# Attenuverting_LinExp_VCA_Bottom.net
KiCad netlist of a schematic drawn in EAGLE
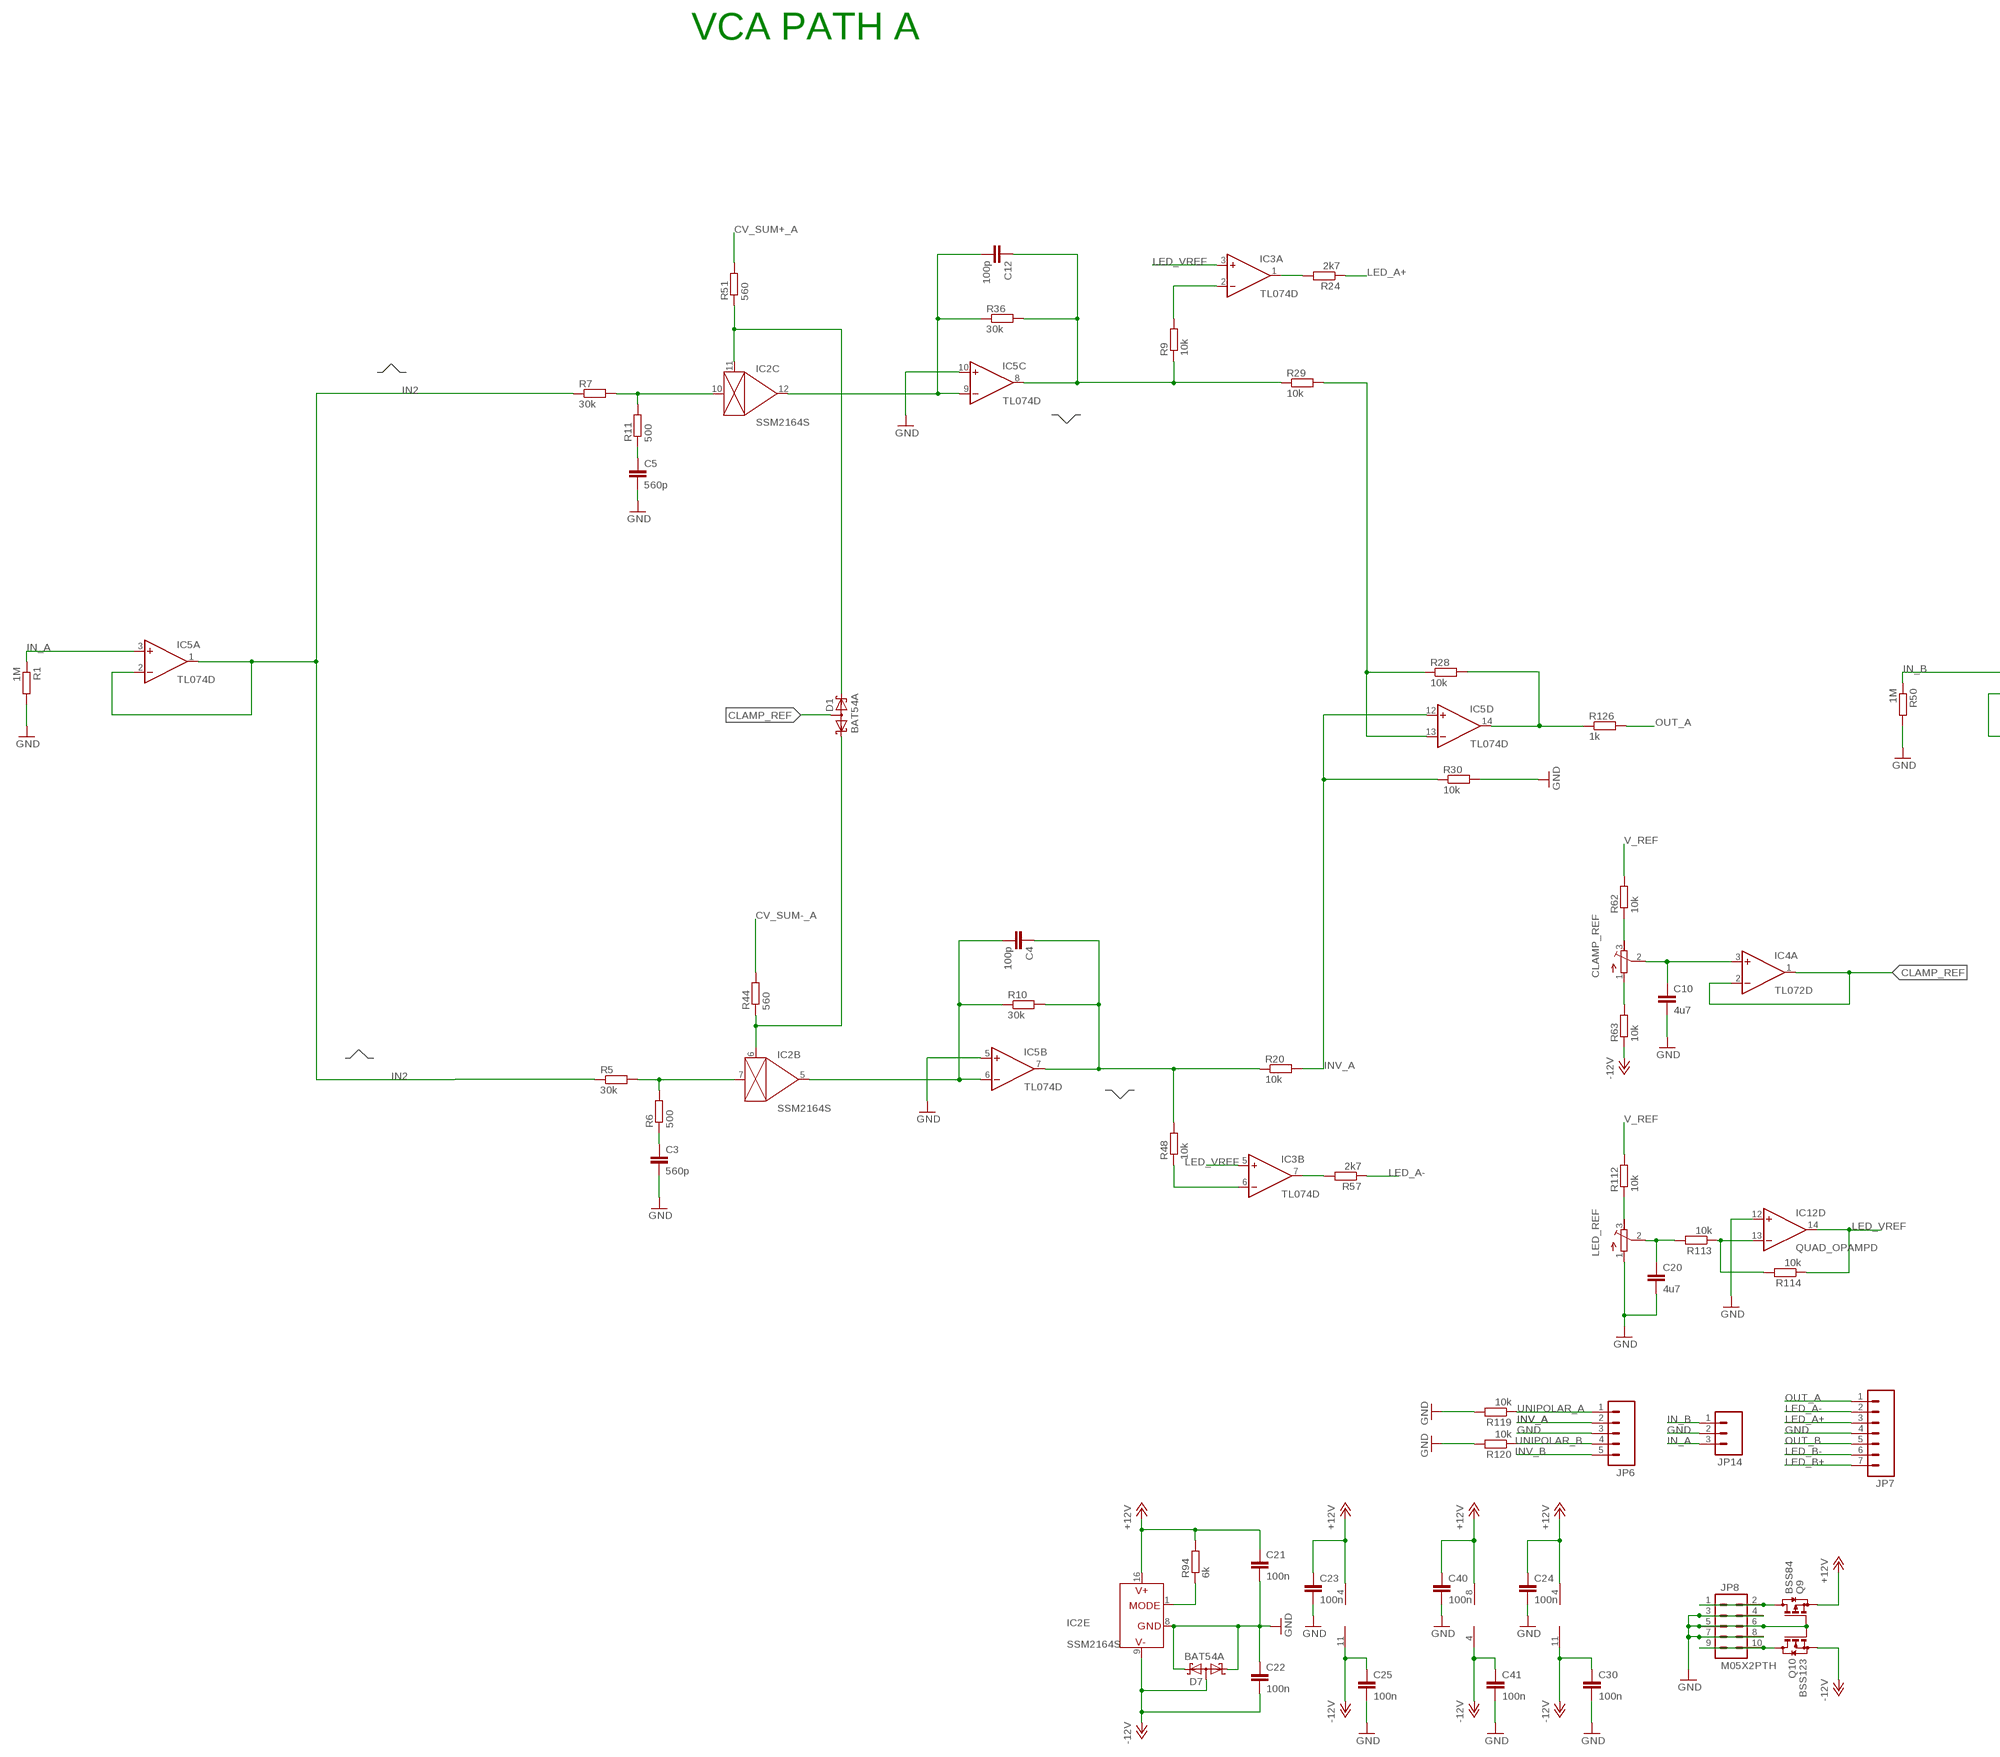
[diagram p0: schematic, sheet 1, part 1 of 2]
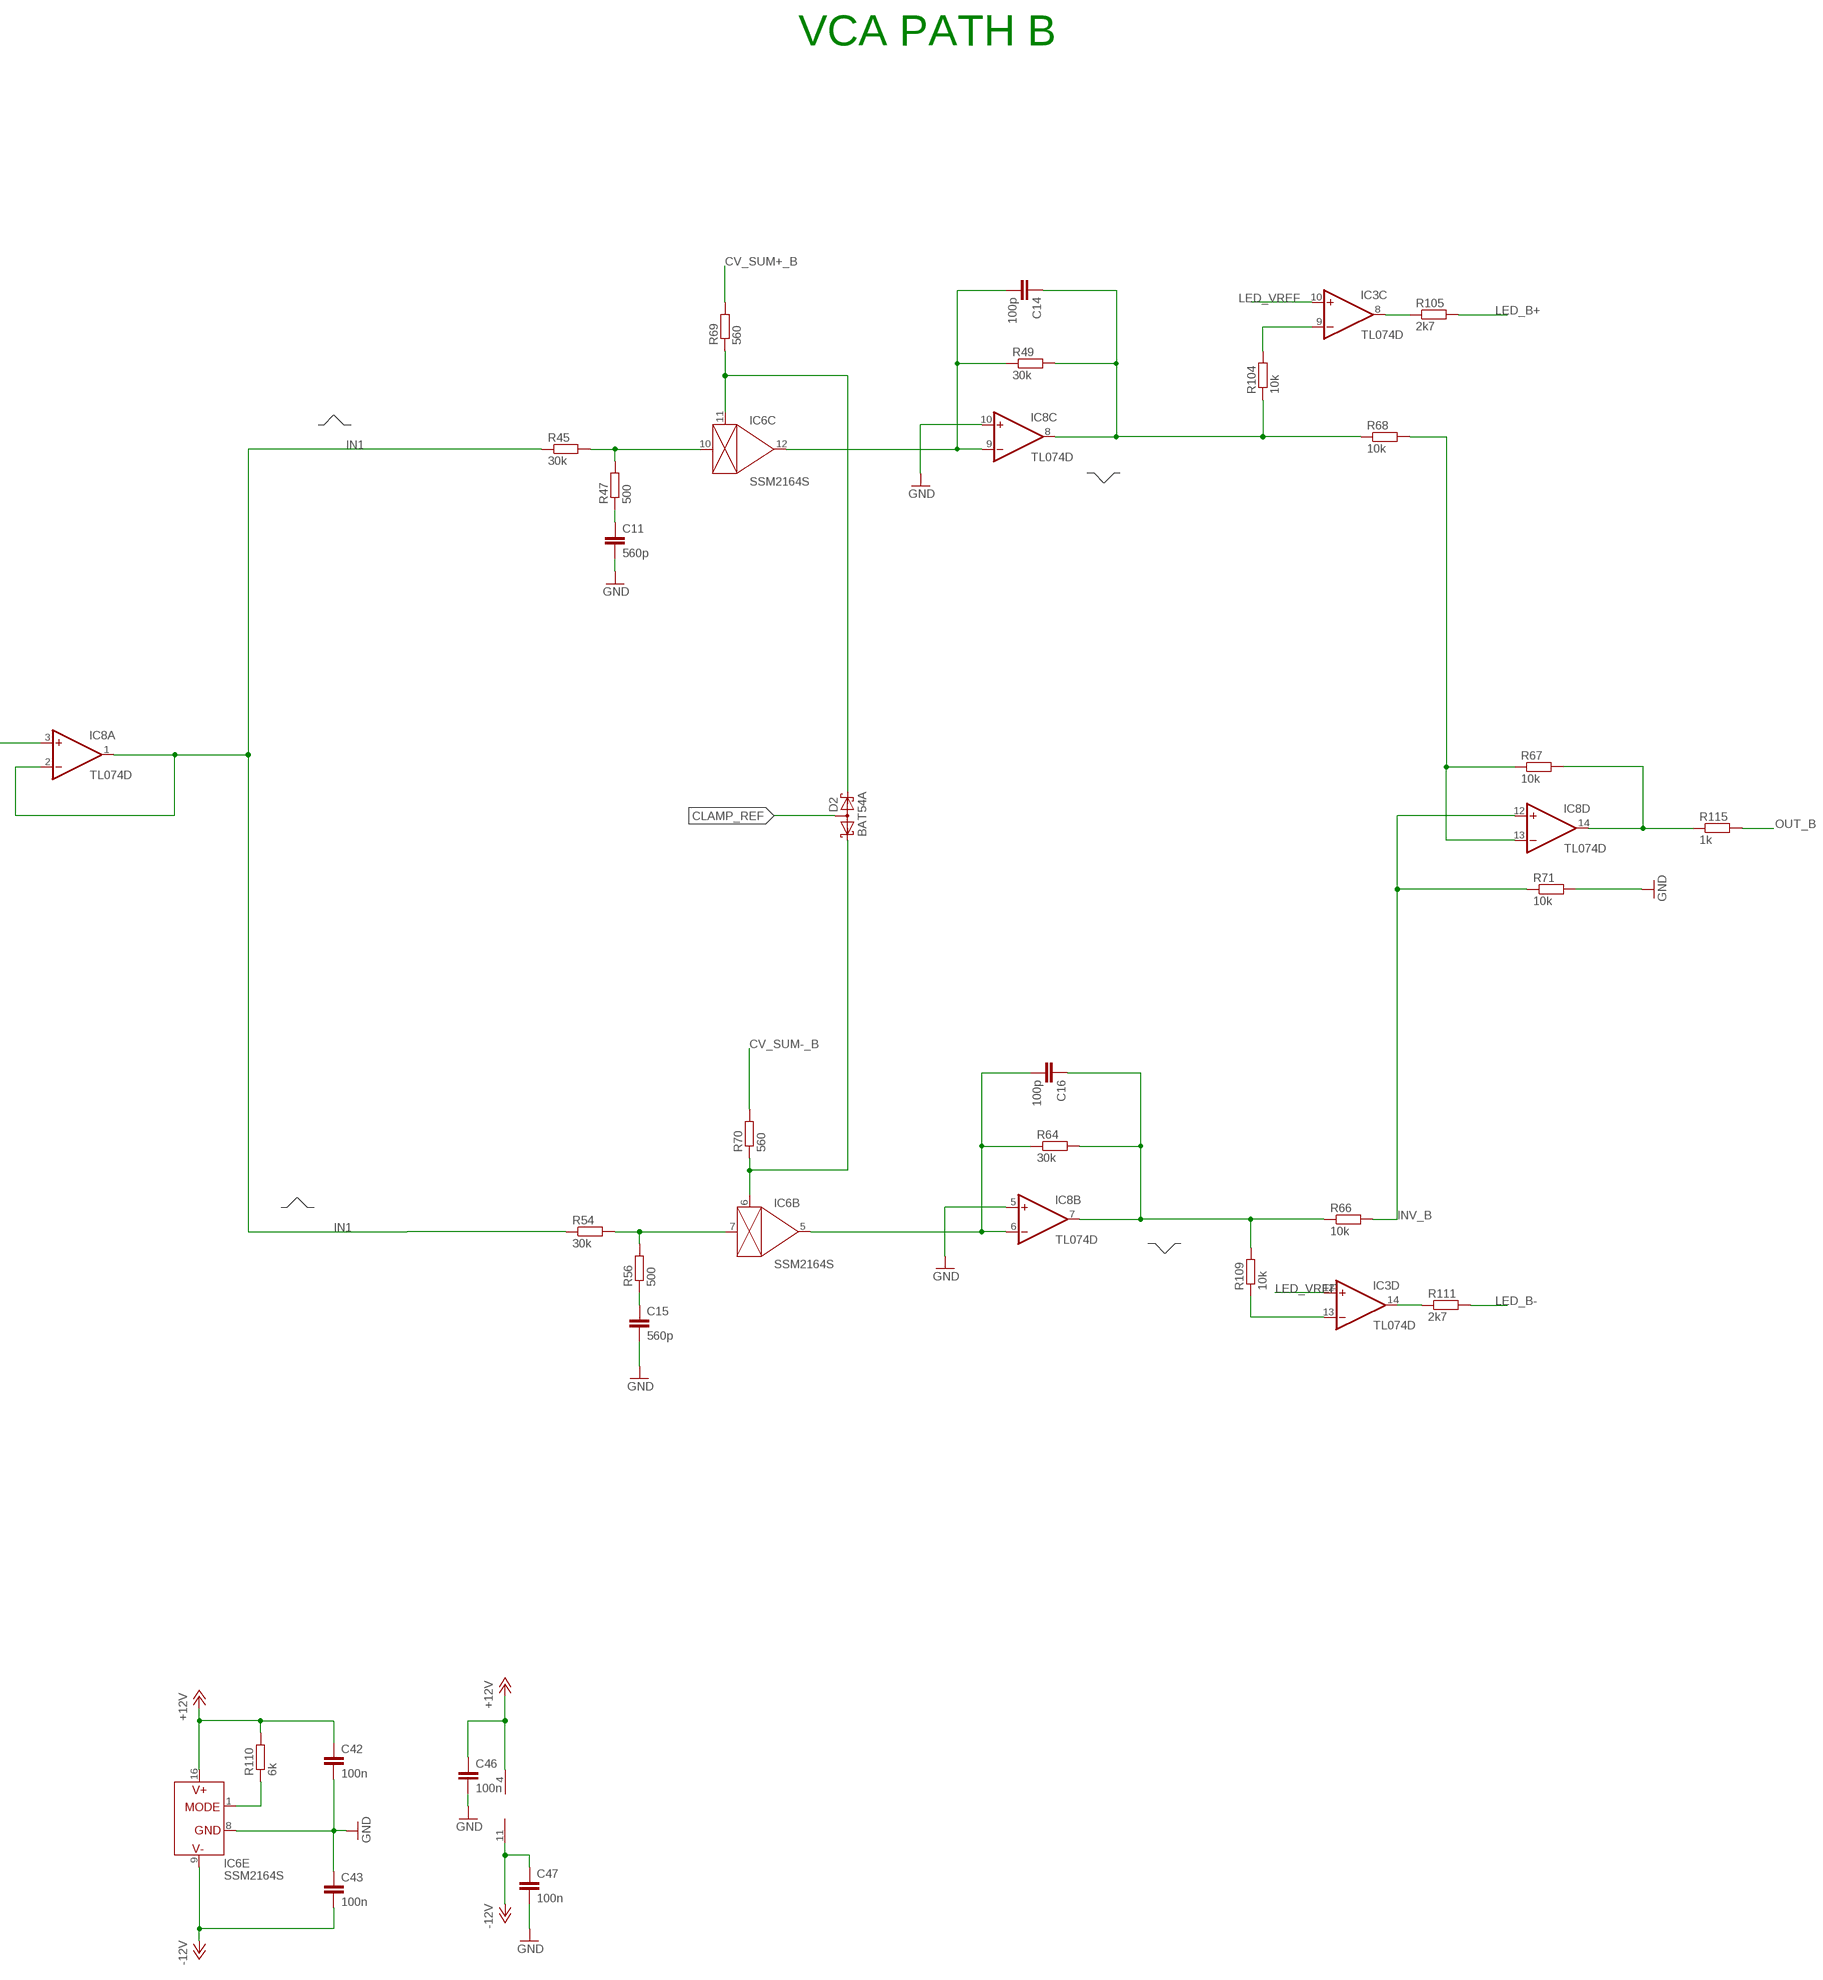
[diagram p1: schematic, sheet 1, part 2 of 2]
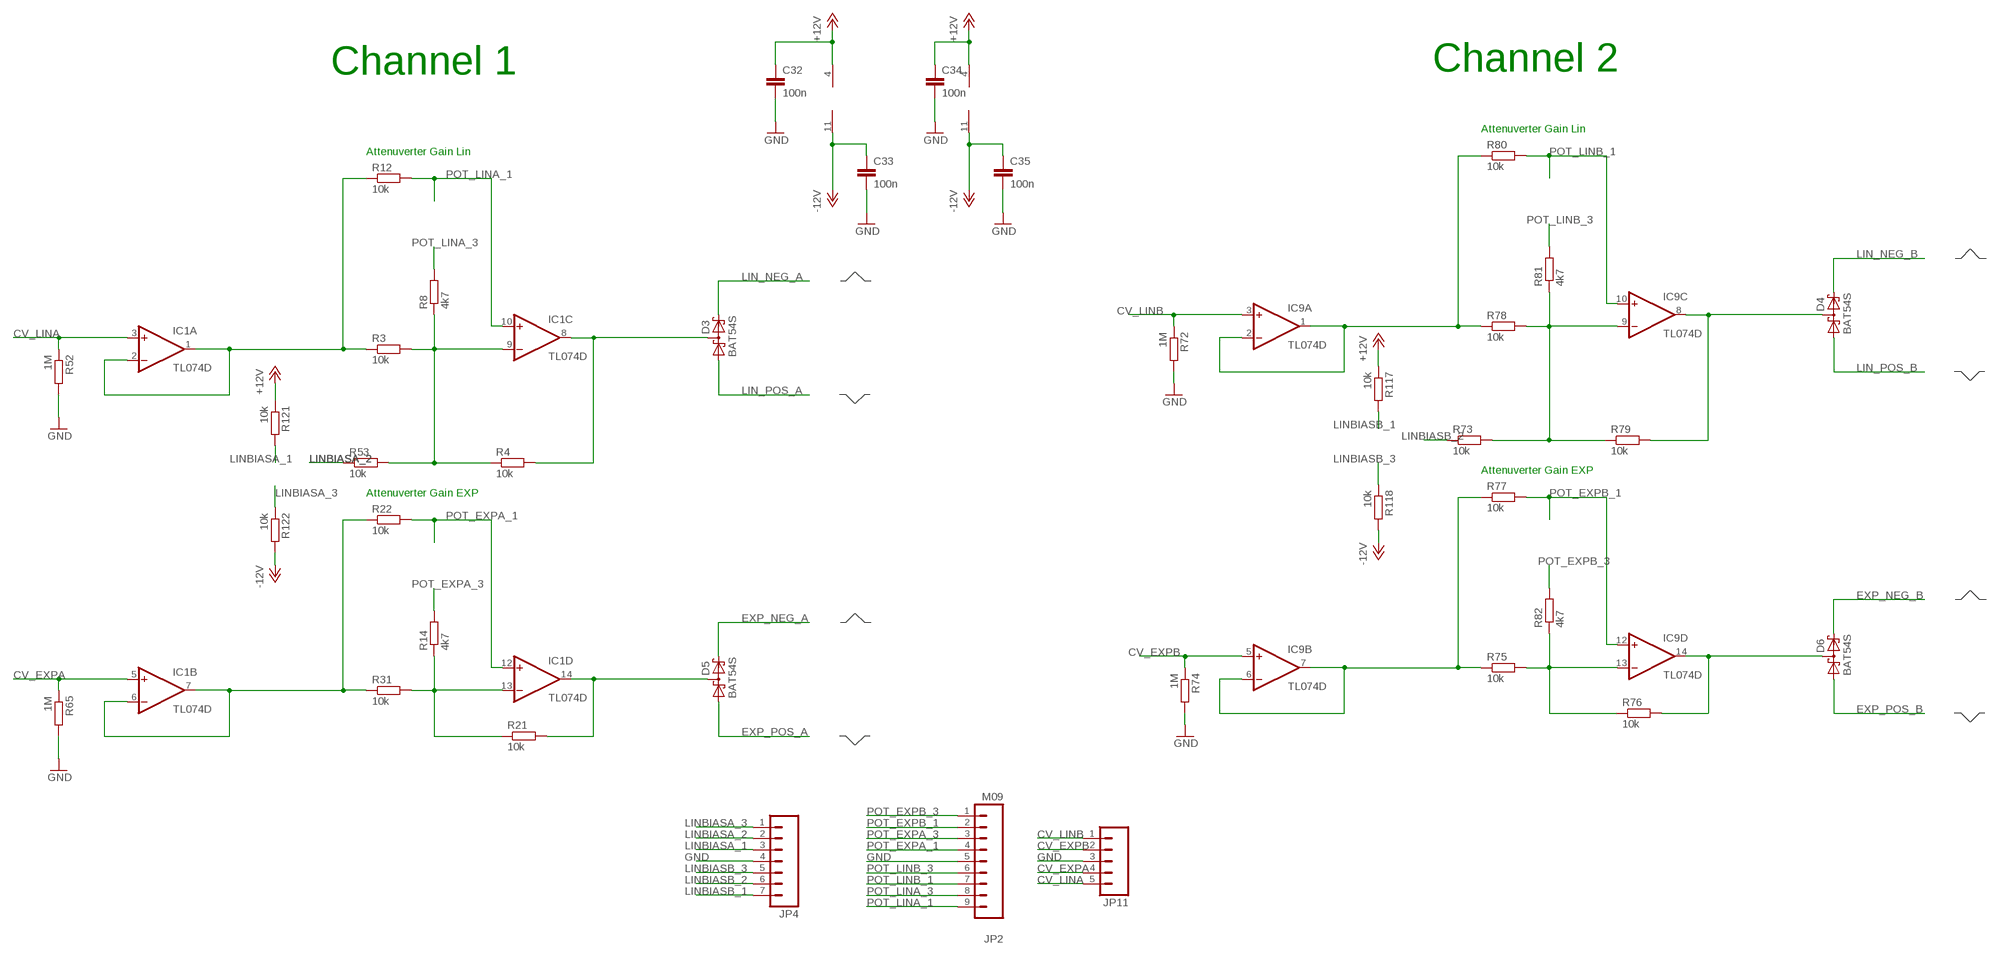
[diagram p2: schematic, sheet 2]
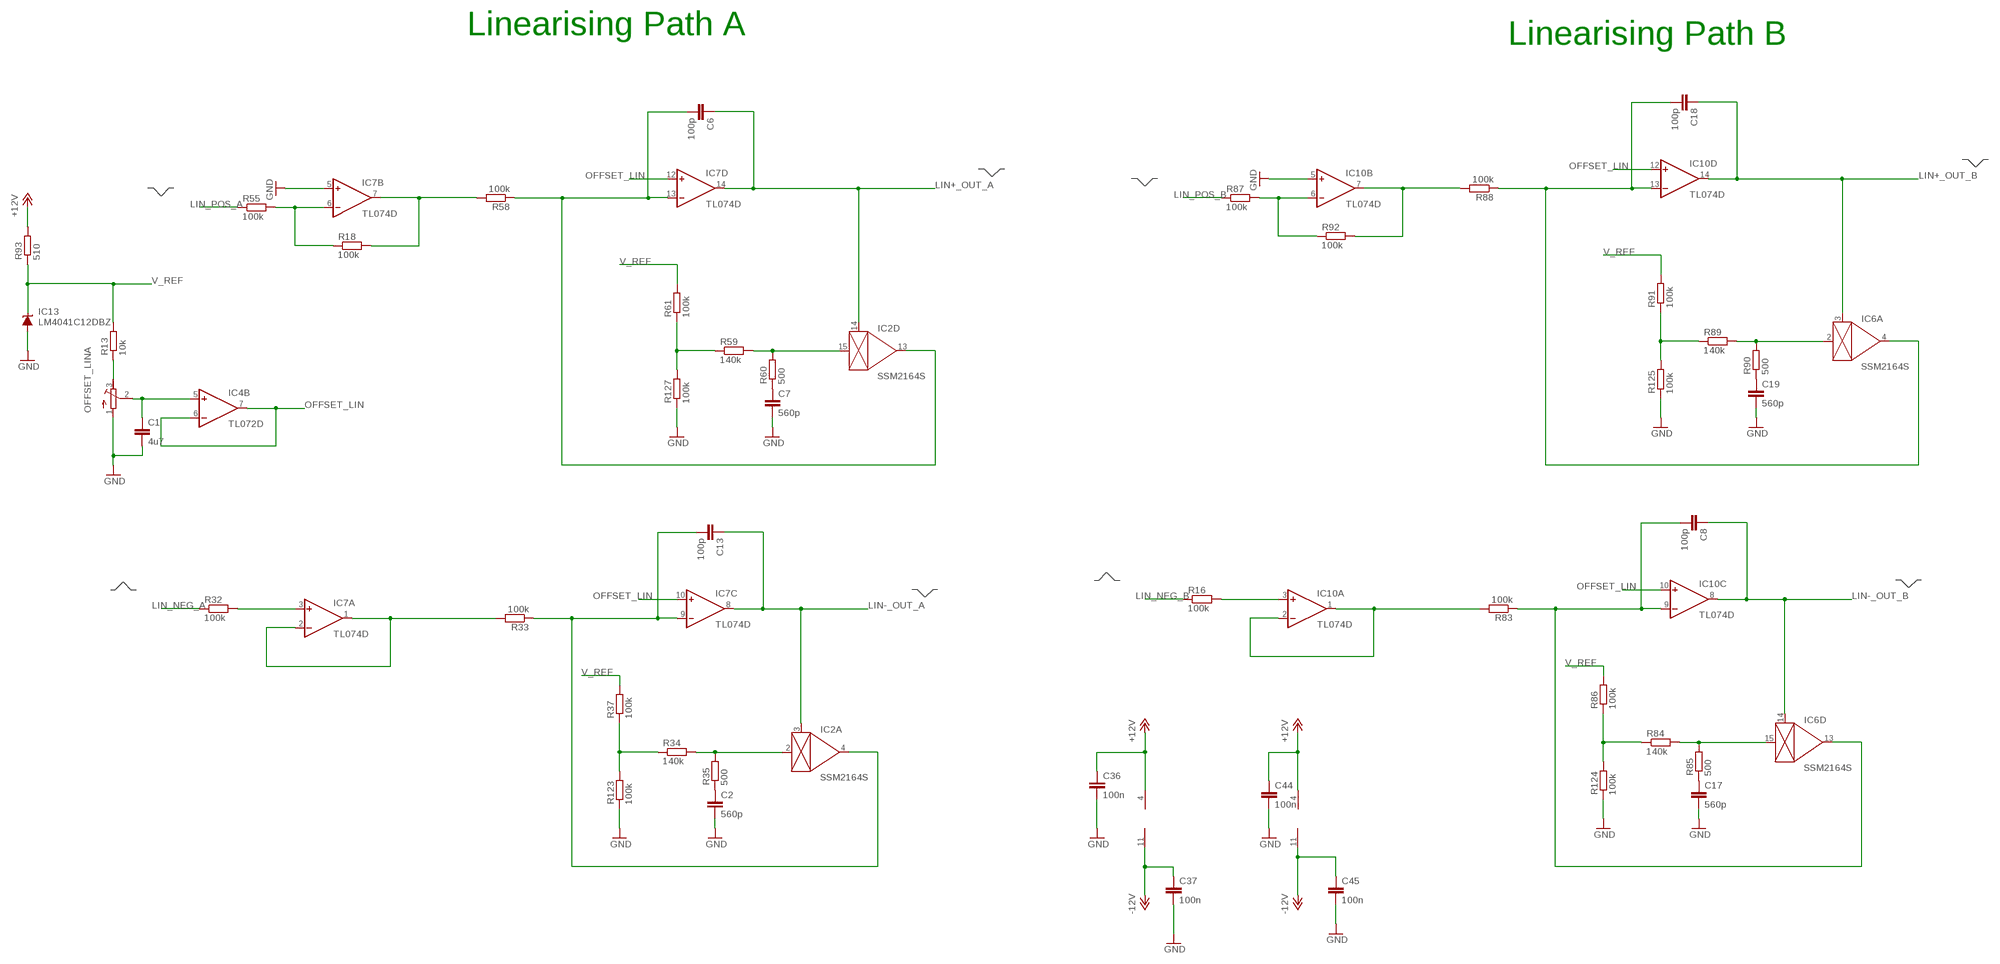
[diagram p3: schematic, sheet 3]
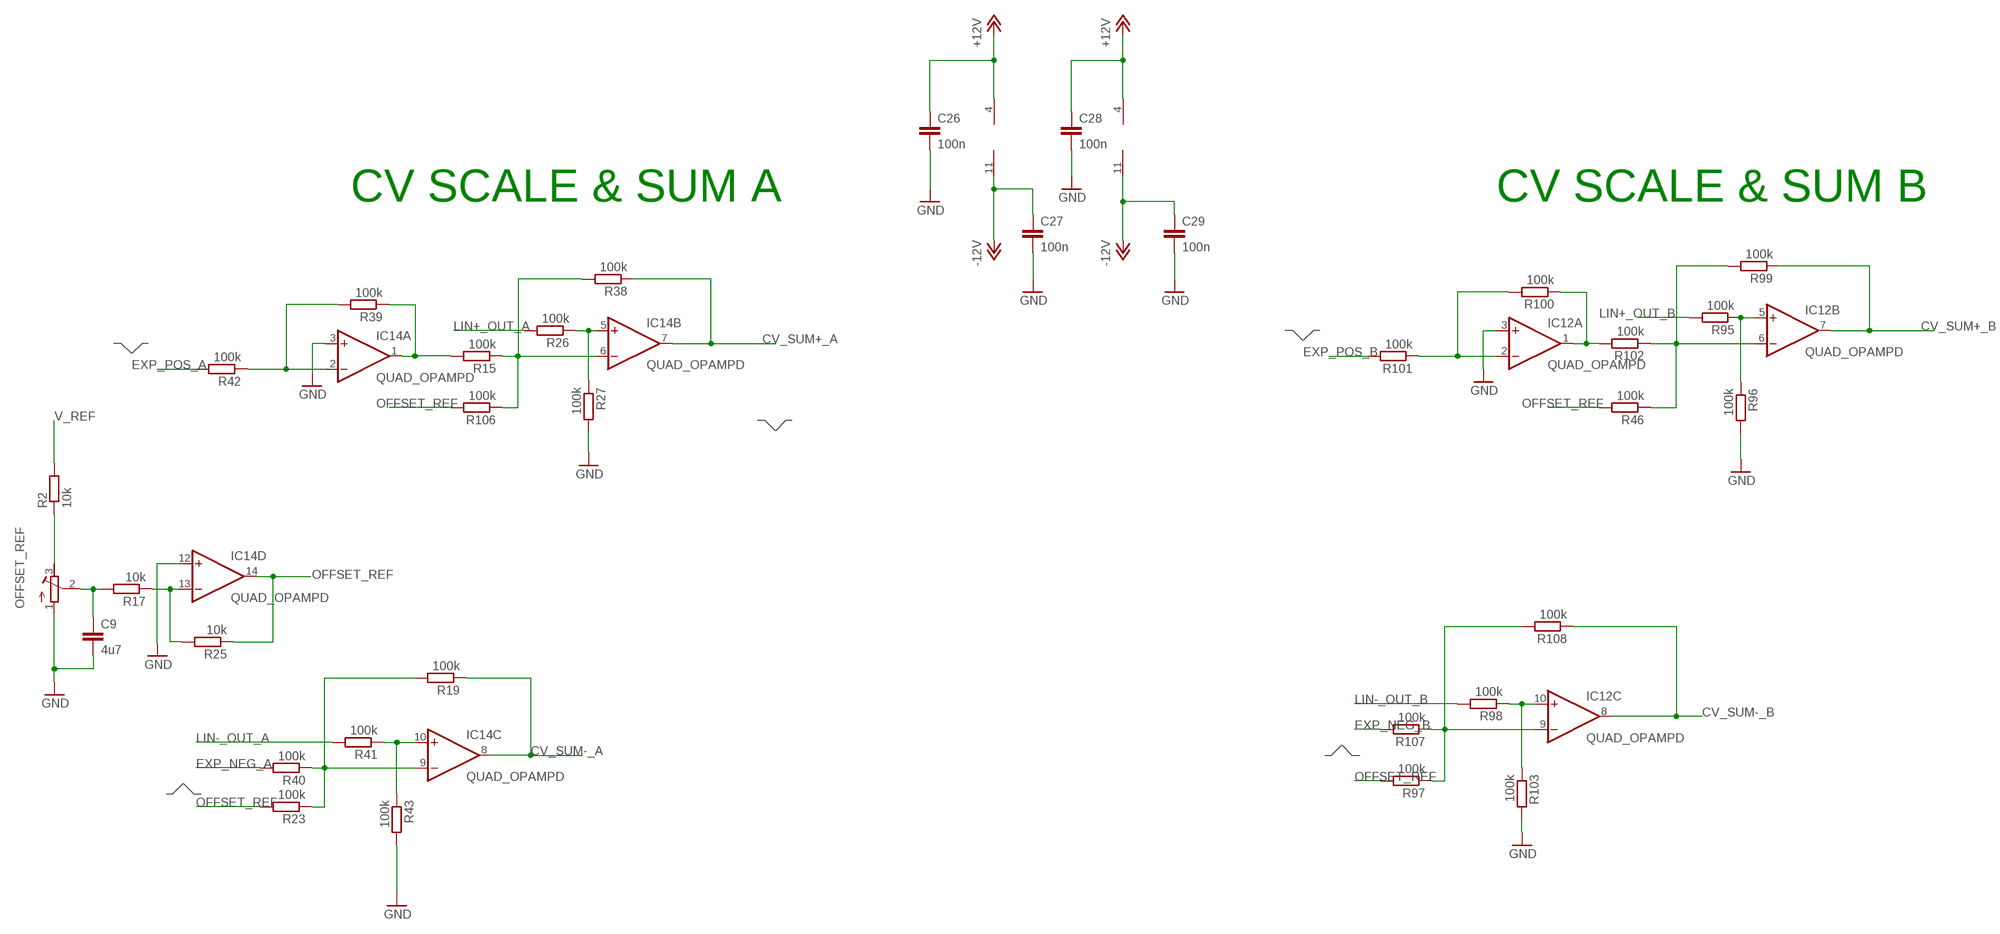
[diagram p4: schematic, sheet 4]

(export (version "E")
  (design (tool "Eeschema 10.0.6"))
  (components
    (comp (ref "C32")
      (value "100n")
      (footprint "eagle-import:C0603K")
      (libsource (lib "eagle-import") (part "C-EUC0603K"))
    )
    (comp (ref "C33")
      (value "100n")
      (footprint "eagle-import:C0603K")
      (libsource (lib "eagle-import") (part "C-EUC0603K"))
    )
    (comp (ref "C34")
      (value "100n")
      (footprint "eagle-import:C0603K")
      (libsource (lib "eagle-import") (part "C-EUC0603K"))
    )
    (comp (ref "C35")
      (value "100n")
      (footprint "eagle-import:C0603K")
      (libsource (lib "eagle-import") (part "C-EUC0603K"))
    )
    (comp (ref "D3")
      (value "BAT54S")
      (footprint "eagle-import:SOT23")
      (libsource (lib "eagle-import") (part "BAT54S"))
    )
    (comp (ref "D4")
      (value "BAT54S")
      (footprint "eagle-import:SOT23")
      (libsource (lib "eagle-import") (part "BAT54S"))
    )
    (comp (ref "D5")
      (value "BAT54S")
      (footprint "eagle-import:SOT23")
      (libsource (lib "eagle-import") (part "BAT54S"))
    )
    (comp (ref "D6")
      (value "BAT54S")
      (footprint "eagle-import:SOT23")
      (libsource (lib "eagle-import") (part "BAT54S"))
    )
    (comp (ref "IC1")
      (value "TL074D")
      (footprint "eagle-import:SO14")
      (fields (field (name "OC_FARNELL") "unknown"))
      (libsource (lib "eagle-import") (part "TL074D"))
    )
    (comp (ref "IC9")
      (value "TL074D")
      (footprint "eagle-import:SO14")
      (fields (field (name "OC_FARNELL") "unknown"))
      (libsource (lib "eagle-import") (part "TL074D"))
    )
    (comp (ref "JP2")
      (value "M09")
      (footprint "eagle-import:1X09")
      (libsource (lib "eagle-import") (part "M09"))
    )
    (comp (ref "JP4")
      (value "M07")
      (footprint "eagle-import:1X07")
      (libsource (lib "eagle-import") (part "M07"))
    )
    (comp (ref "JP11")
      (value "M05PTH")
      (footprint "eagle-import:1X05")
      (libsource (lib "eagle-import") (part "M05PTH"))
    )
    (comp (ref "R3")
      (value "10k")
      (footprint "eagle-import:0603")
      (libsource (lib "eagle-import") (part "R-EU_0603"))
    )
    (comp (ref "R4")
      (value "10k")
      (footprint "eagle-import:0603")
      (libsource (lib "eagle-import") (part "R-EU_0603"))
    )
    (comp (ref "R8")
      (value "4k7")
      (footprint "eagle-import:0603")
      (libsource (lib "eagle-import") (part "R-EU_0603"))
    )
    (comp (ref "R12")
      (value "10k")
      (footprint "eagle-import:0603")
      (libsource (lib "eagle-import") (part "R-EU_0603"))
    )
    (comp (ref "R14")
      (value "4k7")
      (footprint "eagle-import:0603")
      (libsource (lib "eagle-import") (part "R-EU_0603"))
    )
    (comp (ref "R21")
      (value "10k")
      (footprint "eagle-import:0603")
      (libsource (lib "eagle-import") (part "R-EU_0603"))
    )
    (comp (ref "R22")
      (value "10k")
      (footprint "eagle-import:0603")
      (libsource (lib "eagle-import") (part "R-EU_0603"))
    )
    (comp (ref "R31")
      (value "10k")
      (footprint "eagle-import:0603")
      (libsource (lib "eagle-import") (part "R-EU_0603"))
    )
    (comp (ref "R52")
      (value "1M")
      (footprint "eagle-import:0603")
      (libsource (lib "eagle-import") (part "R-EU_0603"))
    )
    (comp (ref "R53")
      (value "10k")
      (footprint "eagle-import:0603")
      (libsource (lib "eagle-import") (part "R-EU_0603"))
    )
    (comp (ref "R65")
      (value "1M")
      (footprint "eagle-import:0603")
      (libsource (lib "eagle-import") (part "R-EU_0603"))
    )
    (comp (ref "R72")
      (value "1M")
      (footprint "eagle-import:0603")
      (libsource (lib "eagle-import") (part "R-EU_0603"))
    )
    (comp (ref "R73")
      (value "10k")
      (footprint "eagle-import:0603")
      (libsource (lib "eagle-import") (part "R-EU_0603"))
    )
    (comp (ref "R74")
      (value "1M")
      (footprint "eagle-import:0603")
      (libsource (lib "eagle-import") (part "R-EU_0603"))
    )
    (comp (ref "R75")
      (value "10k")
      (footprint "eagle-import:0603")
      (libsource (lib "eagle-import") (part "R-EU_0603"))
    )
    (comp (ref "R76")
      (value "10k")
      (footprint "eagle-import:0603")
      (libsource (lib "eagle-import") (part "R-EU_0603"))
    )
    (comp (ref "R77")
      (value "10k")
      (footprint "eagle-import:0603")
      (libsource (lib "eagle-import") (part "R-EU_0603"))
    )
    (comp (ref "R78")
      (value "10k")
      (footprint "eagle-import:0603")
      (libsource (lib "eagle-import") (part "R-EU_0603"))
    )
    (comp (ref "R79")
      (value "10k")
      (footprint "eagle-import:0603")
      (libsource (lib "eagle-import") (part "R-EU_0603"))
    )
    (comp (ref "R80")
      (value "10k")
      (footprint "eagle-import:0603")
      (libsource (lib "eagle-import") (part "R-EU_0603"))
    )
    (comp (ref "R81")
      (value "4k7")
      (footprint "eagle-import:0603")
      (libsource (lib "eagle-import") (part "R-EU_0603"))
    )
    (comp (ref "R82")
      (value "4k7")
      (footprint "eagle-import:0603")
      (libsource (lib "eagle-import") (part "R-EU_0603"))
    )
    (comp (ref "R117")
      (value "10k")
      (footprint "eagle-import:0603")
      (libsource (lib "eagle-import") (part "R-EU_0603"))
    )
    (comp (ref "R118")
      (value "10k")
      (footprint "eagle-import:0603")
      (libsource (lib "eagle-import") (part "R-EU_0603"))
    )
    (comp (ref "R121")
      (value "10k")
      (footprint "eagle-import:0603")
      (libsource (lib "eagle-import") (part "R-EU_0603"))
    )
    (comp (ref "R122")
      (value "10k")
      (footprint "eagle-import:0603")
      (libsource (lib "eagle-import") (part "R-EU_0603"))
    )
    (comp (ref "C9")
      (value "4u7")
      (footprint "eagle-import:C0603K")
      (libsource (lib "eagle-import") (part "resistor_C-EUC0603K"))
    )
    (comp (ref "C26")
      (value "100n")
      (footprint "eagle-import:C0603K")
      (libsource (lib "eagle-import") (part "C-EUC0603K"))
    )
    (comp (ref "C27")
      (value "100n")
      (footprint "eagle-import:C0603K")
      (libsource (lib "eagle-import") (part "C-EUC0603K"))
    )
    (comp (ref "C28")
      (value "100n")
      (footprint "eagle-import:C0603K")
      (libsource (lib "eagle-import") (part "C-EUC0603K"))
    )
    (comp (ref "C29")
      (value "100n")
      (footprint "eagle-import:C0603K")
      (libsource (lib "eagle-import") (part "C-EUC0603K"))
    )
    (comp (ref "IC12")
      (value "QUAD_OPAMPD")
      (footprint "eagle-import:SO14")
      (libsource (lib "eagle-import") (part "QUAD_OPAMPD"))
    )
    (comp (ref "IC14")
      (value "QUAD_OPAMPD")
      (footprint "eagle-import:SO14")
      (libsource (lib "eagle-import") (part "QUAD_OPAMPD"))
    )
    (comp (ref "OFFSET_REF")
      (value "R-TRIMM64W")
      (footprint "eagle-import:RTRIM64W")
      (libsource (lib "eagle-import") (part "R-TRIMM64W"))
    )
    (comp (ref "R2")
      (value "10k")
      (footprint "eagle-import:0603")
      (libsource (lib "eagle-import") (part "R-EU_0603"))
    )
    (comp (ref "R15")
      (value "100k")
      (footprint "eagle-import:0603")
      (libsource (lib "eagle-import") (part "R-EU_0603"))
    )
    (comp (ref "R17")
      (value "10k")
      (footprint "eagle-import:0603")
      (libsource (lib "eagle-import") (part "R-EU_0603"))
    )
    (comp (ref "R19")
      (value "100k")
      (footprint "eagle-import:0603")
      (libsource (lib "eagle-import") (part "R-EU_0603"))
    )
    (comp (ref "R23")
      (value "100k")
      (footprint "eagle-import:0603")
      (libsource (lib "eagle-import") (part "R-EU_0603"))
    )
    (comp (ref "R25")
      (value "10k")
      (footprint "eagle-import:0603")
      (libsource (lib "eagle-import") (part "R-EU_0603"))
    )
    (comp (ref "R26")
      (value "100k")
      (footprint "eagle-import:0603")
      (libsource (lib "eagle-import") (part "R-EU_0603"))
    )
    (comp (ref "R27")
      (value "100k")
      (footprint "eagle-import:0603")
      (libsource (lib "eagle-import") (part "R-EU_0603"))
    )
    (comp (ref "R38")
      (value "100k")
      (footprint "eagle-import:0603")
      (libsource (lib "eagle-import") (part "R-EU_0603"))
    )
    (comp (ref "R39")
      (value "100k")
      (footprint "eagle-import:0603")
      (libsource (lib "eagle-import") (part "R-EU_0603"))
    )
    (comp (ref "R40")
      (value "100k")
      (footprint "eagle-import:0603")
      (libsource (lib "eagle-import") (part "R-EU_0603"))
    )
    (comp (ref "R41")
      (value "100k")
      (footprint "eagle-import:0603")
      (libsource (lib "eagle-import") (part "R-EU_0603"))
    )
    (comp (ref "R42")
      (value "100k")
      (footprint "eagle-import:0603")
      (libsource (lib "eagle-import") (part "R-EU_0603"))
    )
    (comp (ref "R43")
      (value "100k")
      (footprint "eagle-import:0603")
      (libsource (lib "eagle-import") (part "R-EU_0603"))
    )
    (comp (ref "R46")
      (value "100k")
      (footprint "eagle-import:0603")
      (libsource (lib "eagle-import") (part "R-EU_0603"))
    )
    (comp (ref "R95")
      (value "100k")
      (footprint "eagle-import:0603")
      (libsource (lib "eagle-import") (part "R-EU_0603"))
    )
    (comp (ref "R96")
      (value "100k")
      (footprint "eagle-import:0603")
      (libsource (lib "eagle-import") (part "R-EU_0603"))
    )
    (comp (ref "R97")
      (value "100k")
      (footprint "eagle-import:0603")
      (libsource (lib "eagle-import") (part "R-EU_0603"))
    )
    (comp (ref "R98")
      (value "100k")
      (footprint "eagle-import:0603")
      (libsource (lib "eagle-import") (part "R-EU_0603"))
    )
    (comp (ref "R99")
      (value "100k")
      (footprint "eagle-import:0603")
      (libsource (lib "eagle-import") (part "R-EU_0603"))
    )
    (comp (ref "R100")
      (value "100k")
      (footprint "eagle-import:0603")
      (libsource (lib "eagle-import") (part "R-EU_0603"))
    )
    (comp (ref "R101")
      (value "100k")
      (footprint "eagle-import:0603")
      (libsource (lib "eagle-import") (part "R-EU_0603"))
    )
    (comp (ref "R102")
      (value "100k")
      (footprint "eagle-import:0603")
      (libsource (lib "eagle-import") (part "R-EU_0603"))
    )
    (comp (ref "R103")
      (value "100k")
      (footprint "eagle-import:0603")
      (libsource (lib "eagle-import") (part "R-EU_0603"))
    )
    (comp (ref "R106")
      (value "100k")
      (footprint "eagle-import:0603")
      (libsource (lib "eagle-import") (part "R-EU_0603"))
    )
    (comp (ref "R107")
      (value "100k")
      (footprint "eagle-import:0603")
      (libsource (lib "eagle-import") (part "R-EU_0603"))
    )
    (comp (ref "R108")
      (value "100k")
      (footprint "eagle-import:0603")
      (libsource (lib "eagle-import") (part "R-EU_0603"))
    )
    (comp (ref "C1")
      (value "4u7")
      (footprint "eagle-import:C0603K")
      (libsource (lib "eagle-import") (part "resistor_C-EUC0603K"))
    )
    (comp (ref "C2")
      (value "560p")
      (footprint "eagle-import:C0603K")
      (libsource (lib "eagle-import") (part "resistor_C-EUC0603K"))
    )
    (comp (ref "C6")
      (value "100p")
      (footprint "eagle-import:C0603K")
      (libsource (lib "eagle-import") (part "resistor_C-EUC0603K"))
    )
    (comp (ref "C7")
      (value "560p")
      (footprint "eagle-import:C0603K")
      (libsource (lib "eagle-import") (part "resistor_C-EUC0603K"))
    )
    (comp (ref "C8")
      (value "100p")
      (footprint "eagle-import:C0603K")
      (libsource (lib "eagle-import") (part "resistor_C-EUC0603K"))
    )
    (comp (ref "C13")
      (value "100p")
      (footprint "eagle-import:C0603K")
      (libsource (lib "eagle-import") (part "resistor_C-EUC0603K"))
    )
    (comp (ref "C17")
      (value "560p")
      (footprint "eagle-import:C0603K")
      (libsource (lib "eagle-import") (part "resistor_C-EUC0603K"))
    )
    (comp (ref "C18")
      (value "100p")
      (footprint "eagle-import:C0603K")
      (libsource (lib "eagle-import") (part "resistor_C-EUC0603K"))
    )
    (comp (ref "C19")
      (value "560p")
      (footprint "eagle-import:C0603K")
      (libsource (lib "eagle-import") (part "resistor_C-EUC0603K"))
    )
    (comp (ref "C36")
      (value "100n")
      (footprint "eagle-import:C0603K")
      (libsource (lib "eagle-import") (part "rcl@1_C-EUC0603K"))
    )
    (comp (ref "C37")
      (value "100n")
      (footprint "eagle-import:C0603K")
      (libsource (lib "eagle-import") (part "rcl@1_C-EUC0603K"))
    )
    (comp (ref "C44")
      (value "100n")
      (footprint "eagle-import:C0603K")
      (libsource (lib "eagle-import") (part "rcl@1_C-EUC0603K"))
    )
    (comp (ref "C45")
      (value "100n")
      (footprint "eagle-import:C0603K")
      (libsource (lib "eagle-import") (part "rcl@1_C-EUC0603K"))
    )
    (comp (ref "IC2")
      (value "SSM2164S")
      (footprint "eagle-import:SOIC16N")
      (fields (field (name "OC_FARNELL") "unknown"))
      (libsource (lib "eagle-import") (part "SSM2164S"))
    )
    (comp (ref "IC4")
      (value "TL072D")
      (footprint "eagle-import:SO08")
      (libsource (lib "eagle-import") (part "TL072D"))
    )
    (comp (ref "IC6")
      (value "SSM2164S")
      (footprint "eagle-import:SOIC16N")
      (fields (field (name "OC_FARNELL") "unknown"))
      (libsource (lib "eagle-import") (part "SSM2164S"))
    )
    (comp (ref "IC7")
      (value "TL074D")
      (footprint "eagle-import:SO14")
      (fields (field (name "OC_FARNELL") "unknown"))
      (libsource (lib "eagle-import") (part "TL074D"))
    )
    (comp (ref "IC10")
      (value "TL074D")
      (footprint "eagle-import:SO14")
      (fields (field (name "OC_FARNELL") "unknown"))
      (libsource (lib "eagle-import") (part "TL074D"))
    )
    (comp (ref "IC13")
      (value "LM4041C12DBZ")
      (footprint "eagle-import:DBZ_R-PDSO-G3")
      (fields (field (name "MF") "TEXAS INSTRUMENT CONNECTORS") (field (name "MPN") "LM4041C12QDBZT"))
      (libsource (lib "eagle-import") (part "LM4041DBZC12"))
    )
    (comp (ref "OFFSET_LINA")
      (value "R-TRIMM64W")
      (footprint "eagle-import:RTRIM64W")
      (libsource (lib "eagle-import") (part "R-TRIMM64W"))
    )
    (comp (ref "R13")
      (value "10k")
      (footprint "eagle-import:0603")
      (libsource (lib "eagle-import") (part "R-EU_0603"))
    )
    (comp (ref "R16")
      (value "100k")
      (footprint "eagle-import:0603")
      (libsource (lib "eagle-import") (part "R-EU_0603"))
    )
    (comp (ref "R18")
      (value "100k")
      (footprint "eagle-import:0603")
      (libsource (lib "eagle-import") (part "R-EU_0603"))
    )
    (comp (ref "R32")
      (value "100k")
      (footprint "eagle-import:0603")
      (libsource (lib "eagle-import") (part "R-EU_0603"))
    )
    (comp (ref "R33")
      (value "100k")
      (footprint "eagle-import:0603")
      (libsource (lib "eagle-import") (part "R-EU_0603"))
    )
    (comp (ref "R34")
      (value "140k")
      (footprint "eagle-import:0603")
      (libsource (lib "eagle-import") (part "R-EU_0603"))
    )
    (comp (ref "R35")
      (value "500")
      (footprint "eagle-import:0603")
      (libsource (lib "eagle-import") (part "R-EU_0603"))
    )
    (comp (ref "R37")
      (value "100k")
      (footprint "eagle-import:0603")
      (libsource (lib "eagle-import") (part "R-EU_0603"))
    )
    (comp (ref "R55")
      (value "100k")
      (footprint "eagle-import:0603")
      (libsource (lib "eagle-import") (part "R-EU_0603"))
    )
    (comp (ref "R58")
      (value "100k")
      (footprint "eagle-import:0603")
      (libsource (lib "eagle-import") (part "R-EU_0603"))
    )
    (comp (ref "R59")
      (value "140k")
      (footprint "eagle-import:0603")
      (libsource (lib "eagle-import") (part "R-EU_0603"))
    )
    (comp (ref "R60")
      (value "500")
      (footprint "eagle-import:0603")
      (libsource (lib "eagle-import") (part "R-EU_0603"))
    )
    (comp (ref "R61")
      (value "100k")
      (footprint "eagle-import:0603")
      (libsource (lib "eagle-import") (part "R-EU_0603"))
    )
    (comp (ref "R83")
      (value "100k")
      (footprint "eagle-import:0603")
      (libsource (lib "eagle-import") (part "R-EU_0603"))
    )
    (comp (ref "R84")
      (value "140k")
      (footprint "eagle-import:0603")
      (libsource (lib "eagle-import") (part "R-EU_0603"))
    )
    (comp (ref "R85")
      (value "500")
      (footprint "eagle-import:0603")
      (libsource (lib "eagle-import") (part "R-EU_0603"))
    )
    (comp (ref "R86")
      (value "100k")
      (footprint "eagle-import:0603")
      (libsource (lib "eagle-import") (part "R-EU_0603"))
    )
    (comp (ref "R87")
      (value "100k")
      (footprint "eagle-import:0603")
      (libsource (lib "eagle-import") (part "R-EU_0603"))
    )
    (comp (ref "R88")
      (value "100k")
      (footprint "eagle-import:0603")
      (libsource (lib "eagle-import") (part "R-EU_0603"))
    )
    (comp (ref "R89")
      (value "140k")
      (footprint "eagle-import:0603")
      (libsource (lib "eagle-import") (part "R-EU_0603"))
    )
    (comp (ref "R90")
      (value "500")
      (footprint "eagle-import:0603")
      (libsource (lib "eagle-import") (part "R-EU_0603"))
    )
    (comp (ref "R91")
      (value "100k")
      (footprint "eagle-import:0603")
      (libsource (lib "eagle-import") (part "R-EU_0603"))
    )
    (comp (ref "R92")
      (value "100k")
      (footprint "eagle-import:0603")
      (libsource (lib "eagle-import") (part "R-EU_0603"))
    )
    (comp (ref "R93")
      (value "510")
      (footprint "eagle-import:0603")
      (libsource (lib "eagle-import") (part "R-EU_0603"))
    )
    (comp (ref "R123")
      (value "100k")
      (footprint "eagle-import:0603")
      (libsource (lib "eagle-import") (part "R-EU_0603"))
    )
    (comp (ref "R124")
      (value "100k")
      (footprint "eagle-import:0603")
      (libsource (lib "eagle-import") (part "R-EU_0603"))
    )
    (comp (ref "R125")
      (value "100k")
      (footprint "eagle-import:0603")
      (libsource (lib "eagle-import") (part "R-EU_0603"))
    )
    (comp (ref "R127")
      (value "100k")
      (footprint "eagle-import:0603")
      (libsource (lib "eagle-import") (part "R-EU_0603"))
    )
    (comp (ref "C3")
      (value "560p")
      (footprint "eagle-import:C0603K")
      (libsource (lib "eagle-import") (part "resistor_C-EUC0603K"))
    )
    (comp (ref "C4")
      (value "100p")
      (footprint "eagle-import:C0603K")
      (libsource (lib "eagle-import") (part "resistor_C-EUC0603K"))
    )
    (comp (ref "C5")
      (value "560p")
      (footprint "eagle-import:C0603K")
      (libsource (lib "eagle-import") (part "resistor_C-EUC0603K"))
    )
    (comp (ref "C10")
      (value "4u7")
      (footprint "eagle-import:C0603K")
      (libsource (lib "eagle-import") (part "resistor_C-EUC0603K"))
    )
    (comp (ref "C11")
      (value "560p")
      (footprint "eagle-import:C0603K")
      (libsource (lib "eagle-import") (part "resistor_C-EUC0603K"))
    )
    (comp (ref "C12")
      (value "100p")
      (footprint "eagle-import:C0603K")
      (libsource (lib "eagle-import") (part "resistor_C-EUC0603K"))
    )
    (comp (ref "C14")
      (value "100p")
      (footprint "eagle-import:C0603K")
      (libsource (lib "eagle-import") (part "resistor_C-EUC0603K"))
    )
    (comp (ref "C15")
      (value "560p")
      (footprint "eagle-import:C0603K")
      (libsource (lib "eagle-import") (part "resistor_C-EUC0603K"))
    )
    (comp (ref "C16")
      (value "100p")
      (footprint "eagle-import:C0603K")
      (libsource (lib "eagle-import") (part "resistor_C-EUC0603K"))
    )
    (comp (ref "C20")
      (value "4u7")
      (footprint "eagle-import:C0603K")
      (libsource (lib "eagle-import") (part "resistor_C-EUC0603K"))
    )
    (comp (ref "C21")
      (value "100n")
      (footprint "eagle-import:C0603K")
      (libsource (lib "eagle-import") (part "C-EUC0603K"))
    )
    (comp (ref "C22")
      (value "100n")
      (footprint "eagle-import:C0603K")
      (libsource (lib "eagle-import") (part "C-EUC0603K"))
    )
    (comp (ref "C23")
      (value "100n")
      (footprint "eagle-import:C0603K")
      (libsource (lib "eagle-import") (part "C-EUC0603K"))
    )
    (comp (ref "C24")
      (value "100n")
      (footprint "eagle-import:C0603K")
      (libsource (lib "eagle-import") (part "C-EUC0603K"))
    )
    (comp (ref "C25")
      (value "100n")
      (footprint "eagle-import:C0603K")
      (libsource (lib "eagle-import") (part "C-EUC0603K"))
    )
    (comp (ref "C30")
      (value "100n")
      (footprint "eagle-import:C0603K")
      (libsource (lib "eagle-import") (part "C-EUC0603K"))
    )
    (comp (ref "C40")
      (value "100n")
      (footprint "eagle-import:C0603K")
      (libsource (lib "eagle-import") (part "C-EUC0603K"))
    )
    (comp (ref "C41")
      (value "100n")
      (footprint "eagle-import:C0603K")
      (libsource (lib "eagle-import") (part "C-EUC0603K"))
    )
    (comp (ref "C42")
      (value "100n")
      (footprint "eagle-import:C0603K")
      (libsource (lib "eagle-import") (part "C-EUC0603K"))
    )
    (comp (ref "C43")
      (value "100n")
      (footprint "eagle-import:C0603K")
      (libsource (lib "eagle-import") (part "C-EUC0603K"))
    )
    (comp (ref "C46")
      (value "100n")
      (footprint "eagle-import:C0603K")
      (libsource (lib "eagle-import") (part "C-EUC0603K"))
    )
    (comp (ref "C47")
      (value "100n")
      (footprint "eagle-import:C0603K")
      (libsource (lib "eagle-import") (part "C-EUC0603K"))
    )
    (comp (ref "CLAMP_REF")
      (value "R-TRIMM64W")
      (footprint "eagle-import:RTRIM64W")
      (libsource (lib "eagle-import") (part "R-TRIMM64W"))
    )
    (comp (ref "D1")
      (value "BAT54A")
      (footprint "eagle-import:SOT23")
      (libsource (lib "eagle-import") (part "BAT54A"))
    )
    (comp (ref "D2")
      (value "BAT54A")
      (footprint "eagle-import:SOT23")
      (libsource (lib "eagle-import") (part "BAT54A"))
    )
    (comp (ref "D7")
      (value "BAT54A")
      (footprint "eagle-import:SOT23")
      (libsource (lib "eagle-import") (part "BAT54A"))
    )
    (comp (ref "IC3")
      (value "TL074D")
      (footprint "eagle-import:SO14")
      (libsource (lib "eagle-import") (part "linear@1_TL074D"))
    )
    (comp (ref "IC5")
      (value "TL074D")
      (footprint "eagle-import:SO14")
      (fields (field (name "OC_FARNELL") "unknown"))
      (libsource (lib "eagle-import") (part "TL074D"))
    )
    (comp (ref "IC8")
      (value "TL074D")
      (footprint "eagle-import:SO14")
      (fields (field (name "OC_FARNELL") "unknown"))
      (libsource (lib "eagle-import") (part "TL074D"))
    )
    (comp (ref "JP6")
      (value "M05PTH")
      (footprint "eagle-import:1X05")
      (libsource (lib "eagle-import") (part "M05PTH"))
    )
    (comp (ref "JP7")
      (value "M07")
      (footprint "eagle-import:1X07")
      (libsource (lib "eagle-import") (part "M07"))
    )
    (comp (ref "JP8")
      (value "M05X2PTH")
      (footprint "eagle-import:AVR_ICSP")
      (libsource (lib "eagle-import") (part "M05X2PTH"))
    )
    (comp (ref "JP14")
      (value "M03PTH")
      (footprint "eagle-import:1X03")
      (libsource (lib "eagle-import") (part "M03PTH"))
    )
    (comp (ref "LED_REF")
      (value "R-TRIMM64W")
      (footprint "eagle-import:RTRIM64W")
      (libsource (lib "eagle-import") (part "R-TRIMM64W"))
    )
    (comp (ref "Q9")
      (value "BSS84")
      (footprint "eagle-import:SOT23")
      (libsource (lib "eagle-import") (part "BSS84"))
    )
    (comp (ref "Q10")
      (value "BSS123")
      (footprint "eagle-import:SOT23")
      (libsource (lib "eagle-import") (part "BSS123"))
    )
    (comp (ref "R1")
      (value "1M")
      (footprint "eagle-import:0603")
      (libsource (lib "eagle-import") (part "R-EU_0603"))
    )
    (comp (ref "R5")
      (value "30k")
      (footprint "eagle-import:0603")
      (libsource (lib "eagle-import") (part "R-EU_0603"))
    )
    (comp (ref "R6")
      (value "500")
      (footprint "eagle-import:0603")
      (libsource (lib "eagle-import") (part "R-EU_0603"))
    )
    (comp (ref "R7")
      (value "30k")
      (footprint "eagle-import:0603")
      (libsource (lib "eagle-import") (part "R-EU_0603"))
    )
    (comp (ref "R9")
      (value "10k")
      (footprint "eagle-import:0603")
      (libsource (lib "eagle-import") (part "R-EU_0603"))
    )
    (comp (ref "R10")
      (value "30k")
      (footprint "eagle-import:0603")
      (libsource (lib "eagle-import") (part "R-EU_0603"))
    )
    (comp (ref "R11")
      (value "500")
      (footprint "eagle-import:0603")
      (libsource (lib "eagle-import") (part "R-EU_0603"))
    )
    (comp (ref "R20")
      (value "10k")
      (footprint "eagle-import:0603")
      (libsource (lib "eagle-import") (part "R-EU_0603"))
    )
    (comp (ref "R24")
      (value "2k7")
      (footprint "eagle-import:0603")
      (libsource (lib "eagle-import") (part "R-EU_0603"))
    )
    (comp (ref "R28")
      (value "10k")
      (footprint "eagle-import:0603")
      (libsource (lib "eagle-import") (part "R-EU_0603"))
    )
    (comp (ref "R29")
      (value "10k")
      (footprint "eagle-import:0603")
      (libsource (lib "eagle-import") (part "R-EU_0603"))
    )
    (comp (ref "R30")
      (value "10k")
      (footprint "eagle-import:0603")
      (libsource (lib "eagle-import") (part "R-EU_0603"))
    )
    (comp (ref "R36")
      (value "30k")
      (footprint "eagle-import:0603")
      (libsource (lib "eagle-import") (part "R-EU_0603"))
    )
    (comp (ref "R44")
      (value "560")
      (footprint "eagle-import:0603")
      (libsource (lib "eagle-import") (part "R-EU_0603"))
    )
    (comp (ref "R45")
      (value "30k")
      (footprint "eagle-import:0603")
      (libsource (lib "eagle-import") (part "R-EU_0603"))
    )
    (comp (ref "R47")
      (value "500")
      (footprint "eagle-import:0603")
      (libsource (lib "eagle-import") (part "R-EU_0603"))
    )
    (comp (ref "R48")
      (value "10k")
      (footprint "eagle-import:0603")
      (libsource (lib "eagle-import") (part "R-EU_0603"))
    )
    (comp (ref "R49")
      (value "30k")
      (footprint "eagle-import:0603")
      (libsource (lib "eagle-import") (part "R-EU_0603"))
    )
    (comp (ref "R50")
      (value "1M")
      (footprint "eagle-import:0603")
      (libsource (lib "eagle-import") (part "R-EU_0603"))
    )
    (comp (ref "R51")
      (value "560")
      (footprint "eagle-import:0603")
      (libsource (lib "eagle-import") (part "R-EU_0603"))
    )
    (comp (ref "R54")
      (value "30k")
      (footprint "eagle-import:0603")
      (libsource (lib "eagle-import") (part "R-EU_0603"))
    )
    (comp (ref "R56")
      (value "500")
      (footprint "eagle-import:0603")
      (libsource (lib "eagle-import") (part "R-EU_0603"))
    )
    (comp (ref "R57")
      (value "2k7")
      (footprint "eagle-import:0603")
      (libsource (lib "eagle-import") (part "R-EU_0603"))
    )
    (comp (ref "R62")
      (value "10k")
      (footprint "eagle-import:0603")
      (libsource (lib "eagle-import") (part "R-EU_0603"))
    )
    (comp (ref "R63")
      (value "10k")
      (footprint "eagle-import:0603")
      (libsource (lib "eagle-import") (part "R-EU_0603"))
    )
    (comp (ref "R64")
      (value "30k")
      (footprint "eagle-import:0603")
      (libsource (lib "eagle-import") (part "R-EU_0603"))
    )
    (comp (ref "R66")
      (value "10k")
      (footprint "eagle-import:0603")
      (libsource (lib "eagle-import") (part "R-EU_0603"))
    )
    (comp (ref "R67")
      (value "10k")
      (footprint "eagle-import:0603")
      (libsource (lib "eagle-import") (part "R-EU_0603"))
    )
    (comp (ref "R68")
      (value "10k")
      (footprint "eagle-import:0603")
      (libsource (lib "eagle-import") (part "R-EU_0603"))
    )
    (comp (ref "R69")
      (value "560")
      (footprint "eagle-import:0603")
      (libsource (lib "eagle-import") (part "R-EU_0603"))
    )
    (comp (ref "R70")
      (value "560")
      (footprint "eagle-import:0603")
      (libsource (lib "eagle-import") (part "R-EU_0603"))
    )
    (comp (ref "R71")
      (value "10k")
      (footprint "eagle-import:0603")
      (libsource (lib "eagle-import") (part "R-EU_0603"))
    )
    (comp (ref "R94")
      (value "6k")
      (footprint "eagle-import:0603")
      (libsource (lib "eagle-import") (part "R-EU_0603"))
    )
    (comp (ref "R104")
      (value "10k")
      (footprint "eagle-import:0603")
      (libsource (lib "eagle-import") (part "R-EU_0603"))
    )
    (comp (ref "R105")
      (value "2k7")
      (footprint "eagle-import:0603")
      (libsource (lib "eagle-import") (part "R-EU_0603"))
    )
    (comp (ref "R109")
      (value "10k")
      (footprint "eagle-import:0603")
      (libsource (lib "eagle-import") (part "R-EU_0603"))
    )
    (comp (ref "R110")
      (value "6k")
      (footprint "eagle-import:0603")
      (libsource (lib "eagle-import") (part "R-EU_0603"))
    )
    (comp (ref "R111")
      (value "2k7")
      (footprint "eagle-import:0603")
      (libsource (lib "eagle-import") (part "R-EU_0603"))
    )
    (comp (ref "R112")
      (value "10k")
      (footprint "eagle-import:0603")
      (libsource (lib "eagle-import") (part "R-EU_0603"))
    )
    (comp (ref "R113")
      (value "10k")
      (footprint "eagle-import:0603")
      (libsource (lib "eagle-import") (part "R-EU_0603"))
    )
    (comp (ref "R114")
      (value "10k")
      (footprint "eagle-import:0603")
      (libsource (lib "eagle-import") (part "R-EU_0603"))
    )
    (comp (ref "R115")
      (value "1k")
      (footprint "eagle-import:0603")
      (fields (field (name "MF") "MULTICOMP") (field (name "MPN") "MC0063W06031160K"))
      (libsource (lib "eagle-import") (part "R-EU_0603"))
    )
    (comp (ref "R119")
      (value "10k")
      (footprint "eagle-import:0603")
      (libsource (lib "eagle-import") (part "R-EU_0603"))
    )
    (comp (ref "R120")
      (value "10k")
      (footprint "eagle-import:0603")
      (libsource (lib "eagle-import") (part "R-EU_0603"))
    )
    (comp (ref "R126")
      (value "1k")
      (footprint "eagle-import:0603")
      (fields (field (name "MF") "MULTICOMP") (field (name "MPN") "MC0063W06031160K"))
      (libsource (lib "eagle-import") (part "R-EU_0603"))
    )
  )
  (nets
    (net (code "1") (name "+12V") (class "Default")
      (node (ref "C21") (pin "1") (pinfunction "1_1") (pintype "passive"))
      (node (ref "C23") (pin "1") (pinfunction "1_1") (pintype "passive"))
      (node (ref "C24") (pin "1") (pinfunction "1_1") (pintype "passive"))
      (node (ref "C26") (pin "1") (pinfunction "1_1") (pintype "passive"))
      (node (ref "C28") (pin "1") (pinfunction "1_1") (pintype "passive"))
      (node (ref "C32") (pin "1") (pinfunction "1_1") (pintype "passive"))
      (node (ref "C34") (pin "1") (pinfunction "1_1") (pintype "passive"))
      (node (ref "C36") (pin "1") (pinfunction "1_1") (pintype "passive"))
      (node (ref "C40") (pin "1") (pinfunction "1_1") (pintype "passive"))
      (node (ref "C42") (pin "1") (pinfunction "1_1") (pintype "passive"))
      (node (ref "C44") (pin "1") (pinfunction "1_1") (pintype "passive"))
      (node (ref "C46") (pin "1") (pinfunction "1_1") (pintype "passive"))
      (node (ref "IC1") (pin "4") (pinfunction "V+_4") (pintype "power_in"))
      (node (ref "IC10") (pin "4") (pinfunction "V+_4") (pintype "power_in"))
      (node (ref "IC12") (pin "4") (pinfunction "V+_4") (pintype "power_in"))
      (node (ref "IC14") (pin "4") (pinfunction "V+_4") (pintype "power_in"))
      (node (ref "IC2") (pin "16") (pinfunction "V+_16") (pintype "power_in"))
      (node (ref "IC3") (pin "4") (pinfunction "V+_4") (pintype "power_in"))
      (node (ref "IC4") (pin "8") (pinfunction "V+_8") (pintype "power_in"))
      (node (ref "IC5") (pin "4") (pinfunction "V+_4") (pintype "power_in"))
      (node (ref "IC6") (pin "16") (pinfunction "V+_16") (pintype "power_in"))
      (node (ref "IC7") (pin "4") (pinfunction "V+_4") (pintype "power_in"))
      (node (ref "IC8") (pin "4") (pinfunction "V+_4") (pintype "power_in"))
      (node (ref "IC9") (pin "4") (pinfunction "V+_4") (pintype "power_in"))
      (node (ref "Q9") (pin "2") (pinfunction "S_2") (pintype "passive"))
      (node (ref "R110") (pin "2") (pinfunction "2_2") (pintype "passive"))
      (node (ref "R117") (pin "1") (pinfunction "1_1") (pintype "passive"))
      (node (ref "R121") (pin "1") (pinfunction "1_1") (pintype "passive"))
      (node (ref "R93") (pin "2") (pinfunction "2_2") (pintype "passive"))
      (node (ref "R94") (pin "2") (pinfunction "2_2") (pintype "passive"))
    )
    (net (code "2") (name "-12V") (class "Default")
      (node (ref "C22") (pin "2") (pinfunction "2_2") (pintype "passive"))
      (node (ref "C25") (pin "1") (pinfunction "1_1") (pintype "passive"))
      (node (ref "C27") (pin "1") (pinfunction "1_1") (pintype "passive"))
      (node (ref "C29") (pin "1") (pinfunction "1_1") (pintype "passive"))
      (node (ref "C30") (pin "1") (pinfunction "1_1") (pintype "passive"))
      (node (ref "C33") (pin "1") (pinfunction "1_1") (pintype "passive"))
      (node (ref "C35") (pin "1") (pinfunction "1_1") (pintype "passive"))
      (node (ref "C37") (pin "1") (pinfunction "1_1") (pintype "passive"))
      (node (ref "C41") (pin "1") (pinfunction "1_1") (pintype "passive"))
      (node (ref "C43") (pin "2") (pinfunction "2_2") (pintype "passive"))
      (node (ref "C45") (pin "1") (pinfunction "1_1") (pintype "passive"))
      (node (ref "C47") (pin "1") (pinfunction "1_1") (pintype "passive"))
      (node (ref "D7") (pin "3") (pinfunction "AA_3") (pintype "passive"))
      (node (ref "IC1") (pin "11") (pinfunction "V-_11") (pintype "power_in"))
      (node (ref "IC10") (pin "11") (pinfunction "V-_11") (pintype "power_in"))
      (node (ref "IC12") (pin "11") (pinfunction "V-_11") (pintype "power_in"))
      (node (ref "IC14") (pin "11") (pinfunction "V-_11") (pintype "power_in"))
      (node (ref "IC2") (pin "9") (pinfunction "V-_9") (pintype "power_in"))
      (node (ref "IC3") (pin "11") (pinfunction "V-_11") (pintype "power_in"))
      (node (ref "IC4") (pin "4") (pinfunction "V-_4") (pintype "power_in"))
      (node (ref "IC5") (pin "11") (pinfunction "V-_11") (pintype "power_in"))
      (node (ref "IC6") (pin "9") (pinfunction "V-_9") (pintype "power_in"))
      (node (ref "IC7") (pin "11") (pinfunction "V-_11") (pintype "power_in"))
      (node (ref "IC8") (pin "11") (pinfunction "V-_11") (pintype "power_in"))
      (node (ref "IC9") (pin "11") (pinfunction "V-_11") (pintype "power_in"))
      (node (ref "Q10") (pin "2") (pinfunction "S_2") (pintype "passive"))
      (node (ref "R118") (pin "2") (pinfunction "2_2") (pintype "passive"))
      (node (ref "R122") (pin "2") (pinfunction "2_2") (pintype "passive"))
      (node (ref "R63") (pin "1") (pinfunction "1_1") (pintype "passive"))
    )
    (net (code "3") (name "CLAMP_REF") (class "Default")
      (node (ref "D1") (pin "3") (pinfunction "AA_3") (pintype "passive"))
      (node (ref "D2") (pin "3") (pinfunction "AA_3") (pintype "passive"))
      (node (ref "IC4") (pin "1") (pinfunction "OUT_1") (pintype "output"))
      (node (ref "IC4") (pin "2") (pinfunction "-IN_2") (pintype "input"))
    )
    (net (code "4") (name "CV_EXPA") (class "Default")
      (node (ref "IC1") (pin "5") (pinfunction "+IN_5") (pintype "input"))
      (node (ref "JP11") (pin "4") (pinfunction "4_4") (pintype "passive"))
      (node (ref "R65") (pin "1") (pinfunction "1_1") (pintype "passive"))
    )
    (net (code "5") (name "CV_EXPB") (class "Default")
      (node (ref "IC9") (pin "5") (pinfunction "+IN_5") (pintype "input"))
      (node (ref "JP11") (pin "2") (pinfunction "2_2") (pintype "passive"))
      (node (ref "R74") (pin "1") (pinfunction "1_1") (pintype "passive"))
    )
    (net (code "6") (name "CV_LINA") (class "Default")
      (node (ref "IC1") (pin "3") (pinfunction "+IN_3") (pintype "input"))
      (node (ref "JP11") (pin "5") (pinfunction "5_5") (pintype "passive"))
      (node (ref "R52") (pin "1") (pinfunction "1_1") (pintype "passive"))
    )
    (net (code "7") (name "CV_LINB") (class "Default")
      (node (ref "IC9") (pin "3") (pinfunction "+IN_3") (pintype "input"))
      (node (ref "JP11") (pin "1") (pinfunction "1_1") (pintype "passive"))
      (node (ref "R72") (pin "1") (pinfunction "1_1") (pintype "passive"))
    )
    (net (code "8") (name "CV_SUM+_A") (class "Default")
      (node (ref "IC14") (pin "7") (pinfunction "OUT_7") (pintype "output"))
      (node (ref "R38") (pin "1") (pinfunction "1_1") (pintype "passive"))
      (node (ref "R51") (pin "2") (pinfunction "2_2") (pintype "passive"))
    )
    (net (code "9") (name "CV_SUM+_B") (class "Default")
      (node (ref "IC12") (pin "7") (pinfunction "OUT_7") (pintype "output"))
      (node (ref "R69") (pin "2") (pinfunction "2_2") (pintype "passive"))
      (node (ref "R99") (pin "1") (pinfunction "1_1") (pintype "passive"))
    )
    (net (code "10") (name "CV_SUM-_A") (class "Default")
      (node (ref "IC14") (pin "8") (pinfunction "OUT_8") (pintype "output"))
      (node (ref "R19") (pin "1") (pinfunction "1_1") (pintype "passive"))
      (node (ref "R44") (pin "2") (pinfunction "2_2") (pintype "passive"))
    )
    (net (code "11") (name "CV_SUM-_B") (class "Default")
      (node (ref "IC12") (pin "8") (pinfunction "OUT_8") (pintype "output"))
      (node (ref "R108") (pin "1") (pinfunction "1_1") (pintype "passive"))
      (node (ref "R70") (pin "2") (pinfunction "2_2") (pintype "passive"))
    )
    (net (code "12") (name "EXP_NEG_A") (class "Default")
      (node (ref "D5") (pin "2") (pinfunction "C2_2") (pintype "passive"))
      (node (ref "R40") (pin "2") (pinfunction "2_2") (pintype "passive"))
    )
    (net (code "13") (name "EXP_NEG_B") (class "Default")
      (node (ref "D6") (pin "2") (pinfunction "C2_2") (pintype "passive"))
      (node (ref "R107") (pin "2") (pinfunction "2_2") (pintype "passive"))
    )
    (net (code "14") (name "EXP_POS_A") (class "Default")
      (node (ref "D5") (pin "1") (pinfunction "A1_1") (pintype "passive"))
      (node (ref "R42") (pin "2") (pinfunction "2_2") (pintype "passive"))
    )
    (net (code "15") (name "EXP_POS_B") (class "Default")
      (node (ref "D6") (pin "1") (pinfunction "A1_1") (pintype "passive"))
      (node (ref "R101") (pin "2") (pinfunction "2_2") (pintype "passive"))
    )
    (net (code "16") (name "GND") (class "Default")
      (node (ref "C1") (pin "2") (pinfunction "2_2") (pintype "passive"))
      (node (ref "C10") (pin "2") (pinfunction "2_2") (pintype "passive"))
      (node (ref "C11") (pin "2") (pinfunction "2_2") (pintype "passive"))
      (node (ref "C15") (pin "2") (pinfunction "2_2") (pintype "passive"))
      (node (ref "C17") (pin "2") (pinfunction "2_2") (pintype "passive"))
      (node (ref "C19") (pin "2") (pinfunction "2_2") (pintype "passive"))
      (node (ref "C2") (pin "2") (pinfunction "2_2") (pintype "passive"))
      (node (ref "C20") (pin "2") (pinfunction "2_2") (pintype "passive"))
      (node (ref "C21") (pin "2") (pinfunction "2_2") (pintype "passive"))
      (node (ref "C22") (pin "1") (pinfunction "1_1") (pintype "passive"))
      (node (ref "C23") (pin "2") (pinfunction "2_2") (pintype "passive"))
      (node (ref "C24") (pin "2") (pinfunction "2_2") (pintype "passive"))
      (node (ref "C25") (pin "2") (pinfunction "2_2") (pintype "passive"))
      (node (ref "C26") (pin "2") (pinfunction "2_2") (pintype "passive"))
      (node (ref "C27") (pin "2") (pinfunction "2_2") (pintype "passive"))
      (node (ref "C28") (pin "2") (pinfunction "2_2") (pintype "passive"))
      (node (ref "C29") (pin "2") (pinfunction "2_2") (pintype "passive"))
      (node (ref "C3") (pin "2") (pinfunction "2_2") (pintype "passive"))
      (node (ref "C30") (pin "2") (pinfunction "2_2") (pintype "passive"))
      (node (ref "C32") (pin "2") (pinfunction "2_2") (pintype "passive"))
      (node (ref "C33") (pin "2") (pinfunction "2_2") (pintype "passive"))
      (node (ref "C34") (pin "2") (pinfunction "2_2") (pintype "passive"))
      (node (ref "C35") (pin "2") (pinfunction "2_2") (pintype "passive"))
      (node (ref "C36") (pin "2") (pinfunction "2_2") (pintype "passive"))
      (node (ref "C37") (pin "2") (pinfunction "2_2") (pintype "passive"))
      (node (ref "C40") (pin "2") (pinfunction "2_2") (pintype "passive"))
      (node (ref "C41") (pin "2") (pinfunction "2_2") (pintype "passive"))
      (node (ref "C42") (pin "2") (pinfunction "2_2") (pintype "passive"))
      (node (ref "C43") (pin "1") (pinfunction "1_1") (pintype "passive"))
      (node (ref "C44") (pin "2") (pinfunction "2_2") (pintype "passive"))
      (node (ref "C45") (pin "2") (pinfunction "2_2") (pintype "passive"))
      (node (ref "C46") (pin "2") (pinfunction "2_2") (pintype "passive"))
      (node (ref "C47") (pin "2") (pinfunction "2_2") (pintype "passive"))
      (node (ref "C5") (pin "2") (pinfunction "2_2") (pintype "passive"))
      (node (ref "C7") (pin "2") (pinfunction "2_2") (pintype "passive"))
      (node (ref "C9") (pin "2") (pinfunction "2_2") (pintype "passive"))
      (node (ref "D7") (pin "1") (pinfunction "K1_1") (pintype "passive"))
      (node (ref "D7") (pin "2") (pinfunction "K2_2") (pintype "passive"))
      (node (ref "IC10") (pin "5") (pinfunction "+IN_5") (pintype "input"))
      (node (ref "IC12") (pin "12") (pinfunction "+IN_12") (pintype "input"))
      (node (ref "IC12") (pin "3") (pinfunction "+IN_3") (pintype "input"))
      (node (ref "IC13") (pin "2") (pinfunction "A_2") (pintype "passive"))
      (node (ref "IC14") (pin "12") (pinfunction "+IN_12") (pintype "input"))
      (node (ref "IC14") (pin "3") (pinfunction "+IN_3") (pintype "input"))
      (node (ref "IC2") (pin "8") (pinfunction "GND_8") (pintype "power_in"))
      (node (ref "IC5") (pin "10") (pinfunction "+IN_10") (pintype "input"))
      (node (ref "IC5") (pin "5") (pinfunction "+IN_5") (pintype "input"))
      (node (ref "IC6") (pin "8") (pinfunction "GND_8") (pintype "power_in"))
      (node (ref "IC7") (pin "5") (pinfunction "+IN_5") (pintype "input"))
      (node (ref "IC8") (pin "10") (pinfunction "+IN_10") (pintype "input"))
      (node (ref "IC8") (pin "5") (pinfunction "+IN_5") (pintype "input"))
      (node (ref "JP11") (pin "3") (pinfunction "3_3") (pintype "passive"))
      (node (ref "JP14") (pin "2") (pinfunction "2_2") (pintype "passive"))
      (node (ref "JP2") (pin "5") (pinfunction "5_5") (pintype "passive"))
      (node (ref "JP4") (pin "4") (pinfunction "4_4") (pintype "passive"))
      (node (ref "JP6") (pin "3") (pinfunction "3_3") (pintype "passive"))
      (node (ref "JP7") (pin "4") (pinfunction "4_4") (pintype "passive"))
      (node (ref "JP8") (pin "3") (pinfunction "3_3") (pintype "passive"))
      (node (ref "JP8") (pin "4") (pinfunction "4_4") (pintype "passive"))
      (node (ref "JP8") (pin "5") (pinfunction "5_5") (pintype "passive"))
      (node (ref "JP8") (pin "6") (pinfunction "6_6") (pintype "passive"))
      (node (ref "JP8") (pin "7") (pinfunction "7_7") (pintype "passive"))
      (node (ref "JP8") (pin "8") (pinfunction "8_8") (pintype "passive"))
      (node (ref "LED_REF") (pin "1") (pinfunction "A_1") (pintype "passive"))
      (node (ref "OFFSET_LINA") (pin "1") (pinfunction "A_1") (pintype "passive"))
      (node (ref "OFFSET_REF") (pin "1") (pinfunction "A_1") (pintype "passive"))
      (node (ref "Q10") (pin "1") (pinfunction "G_1") (pintype "passive"))
      (node (ref "Q9") (pin "1") (pinfunction "G_1") (pintype "passive"))
      (node (ref "R1") (pin "2") (pinfunction "2_2") (pintype "passive"))
      (node (ref "R103") (pin "2") (pinfunction "2_2") (pintype "passive"))
      (node (ref "R119") (pin "2") (pinfunction "2_2") (pintype "passive"))
      (node (ref "R120") (pin "2") (pinfunction "2_2") (pintype "passive"))
      (node (ref "R123") (pin "1") (pinfunction "1_1") (pintype "passive"))
      (node (ref "R124") (pin "1") (pinfunction "1_1") (pintype "passive"))
      (node (ref "R125") (pin "1") (pinfunction "1_1") (pintype "passive"))
      (node (ref "R127") (pin "1") (pinfunction "1_1") (pintype "passive"))
      (node (ref "R27") (pin "2") (pinfunction "2_2") (pintype "passive"))
      (node (ref "R30") (pin "2") (pinfunction "2_2") (pintype "passive"))
      (node (ref "R43") (pin "2") (pinfunction "2_2") (pintype "passive"))
      (node (ref "R50") (pin "2") (pinfunction "2_2") (pintype "passive"))
      (node (ref "R52") (pin "2") (pinfunction "2_2") (pintype "passive"))
      (node (ref "R65") (pin "2") (pinfunction "2_2") (pintype "passive"))
      (node (ref "R71") (pin "2") (pinfunction "2_2") (pintype "passive"))
      (node (ref "R72") (pin "2") (pinfunction "2_2") (pintype "passive"))
      (node (ref "R74") (pin "2") (pinfunction "2_2") (pintype "passive"))
      (node (ref "R96") (pin "2") (pinfunction "2_2") (pintype "passive"))
    )
    (net (code "17") (name "IN1") (class "Default")
      (node (ref "IC8") (pin "1") (pinfunction "OUT_1") (pintype "output"))
      (node (ref "IC8") (pin "2") (pinfunction "-IN_2") (pintype "input"))
      (node (ref "R45") (pin "1") (pinfunction "1_1") (pintype "passive"))
      (node (ref "R54") (pin "1") (pinfunction "1_1") (pintype "passive"))
    )
    (net (code "18") (name "IN2") (class "Default")
      (node (ref "IC5") (pin "1") (pinfunction "OUT_1") (pintype "output"))
      (node (ref "IC5") (pin "2") (pinfunction "-IN_2") (pintype "input"))
      (node (ref "R5") (pin "1") (pinfunction "1_1") (pintype "passive"))
      (node (ref "R7") (pin "1") (pinfunction "1_1") (pintype "passive"))
    )
    (net (code "19") (name "INV_A") (class "Default")
      (node (ref "IC5") (pin "12") (pinfunction "+IN_12") (pintype "input"))
      (node (ref "JP6") (pin "2") (pinfunction "2_2") (pintype "passive"))
      (node (ref "R20") (pin "2") (pinfunction "2_2") (pintype "passive"))
      (node (ref "R30") (pin "1") (pinfunction "1_1") (pintype "passive"))
    )
    (net (code "20") (name "INV_B") (class "Default")
      (node (ref "IC8") (pin "12") (pinfunction "+IN_12") (pintype "input"))
      (node (ref "JP6") (pin "5") (pinfunction "5_5") (pintype "passive"))
      (node (ref "R66") (pin "2") (pinfunction "2_2") (pintype "passive"))
      (node (ref "R71") (pin "1") (pinfunction "1_1") (pintype "passive"))
    )
    (net (code "21") (name "IN_A") (class "Default")
      (node (ref "IC5") (pin "3") (pinfunction "+IN_3") (pintype "input"))
      (node (ref "JP14") (pin "3") (pinfunction "3_3") (pintype "passive"))
      (node (ref "R1") (pin "1") (pinfunction "1_1") (pintype "passive"))
    )
    (net (code "22") (name "IN_B") (class "Default")
      (node (ref "IC8") (pin "3") (pinfunction "+IN_3") (pintype "input"))
      (node (ref "JP14") (pin "1") (pinfunction "1_1") (pintype "passive"))
      (node (ref "R50") (pin "1") (pinfunction "1_1") (pintype "passive"))
    )
    (net (code "23") (name "LED_A+") (class "Default")
      (node (ref "JP7") (pin "3") (pinfunction "3_3") (pintype "passive"))
      (node (ref "R24") (pin "1") (pinfunction "1_1") (pintype "passive"))
    )
    (net (code "24") (name "LED_A-") (class "Default")
      (node (ref "JP7") (pin "2") (pinfunction "2_2") (pintype "passive"))
      (node (ref "R57") (pin "1") (pinfunction "1_1") (pintype "passive"))
    )
    (net (code "25") (name "LED_B+") (class "Default")
      (node (ref "JP7") (pin "7") (pinfunction "7_7") (pintype "passive"))
      (node (ref "R105") (pin "2") (pinfunction "2_2") (pintype "passive"))
    )
    (net (code "26") (name "LED_B-") (class "Default")
      (node (ref "JP7") (pin "6") (pinfunction "6_6") (pintype "passive"))
      (node (ref "R111") (pin "2") (pinfunction "2_2") (pintype "passive"))
    )
    (net (code "27") (name "LED_VREF") (class "Default")
      (node (ref "IC12") (pin "14") (pinfunction "OUT_14") (pintype "output"))
      (node (ref "IC3") (pin "10") (pinfunction "+IN_10") (pintype "input"))
      (node (ref "IC3") (pin "12") (pinfunction "+IN_12") (pintype "input"))
      (node (ref "IC3") (pin "3") (pinfunction "+IN_3") (pintype "input"))
      (node (ref "IC3") (pin "5") (pinfunction "+IN_5") (pintype "input"))
      (node (ref "R114") (pin "1") (pinfunction "1_1") (pintype "passive"))
    )
    (net (code "28") (name "LIN+_OUT_A") (class "Default")
      (node (ref "C6") (pin "1") (pinfunction "1_1") (pintype "passive"))
      (node (ref "IC2") (pin "14") (pinfunction "CTRL_14") (pintype "input"))
      (node (ref "IC7") (pin "14") (pinfunction "OUT_14") (pintype "output"))
      (node (ref "R26") (pin "2") (pinfunction "2_2") (pintype "passive"))
    )
    (net (code "29") (name "LIN+_OUT_B") (class "Default")
      (node (ref "C18") (pin "1") (pinfunction "1_1") (pintype "passive"))
      (node (ref "IC10") (pin "14") (pinfunction "OUT_14") (pintype "output"))
      (node (ref "IC6") (pin "3") (pinfunction "CTRL_3") (pintype "input"))
      (node (ref "R95") (pin "2") (pinfunction "2_2") (pintype "passive"))
    )
    (net (code "30") (name "LIN-_OUT_A") (class "Default")
      (node (ref "C13") (pin "1") (pinfunction "1_1") (pintype "passive"))
      (node (ref "IC2") (pin "3") (pinfunction "CTRL_3") (pintype "input"))
      (node (ref "IC7") (pin "8") (pinfunction "OUT_8") (pintype "output"))
      (node (ref "R41") (pin "2") (pinfunction "2_2") (pintype "passive"))
    )
    (net (code "31") (name "LIN-_OUT_B") (class "Default")
      (node (ref "C8") (pin "1") (pinfunction "1_1") (pintype "passive"))
      (node (ref "IC10") (pin "8") (pinfunction "OUT_8") (pintype "output"))
      (node (ref "IC6") (pin "14") (pinfunction "CTRL_14") (pintype "input"))
      (node (ref "R98") (pin "2") (pinfunction "2_2") (pintype "passive"))
    )
    (net (code "32") (name "LINBIASA_1") (class "Default")
      (node (ref "JP4") (pin "3") (pinfunction "3_3") (pintype "passive"))
      (node (ref "R121") (pin "2") (pinfunction "2_2") (pintype "passive"))
    )
    (net (code "33") (name "LINBIASA_2") (class "Default")
      (node (ref "JP4") (pin "2") (pinfunction "2_2") (pintype "passive"))
      (node (ref "R53") (pin "1") (pinfunction "1_1") (pintype "passive"))
    )
    (net (code "34") (name "LINBIASA_3") (class "Default")
      (node (ref "JP4") (pin "1") (pinfunction "1_1") (pintype "passive"))
      (node (ref "R122") (pin "1") (pinfunction "1_1") (pintype "passive"))
    )
    (net (code "35") (name "LINBIASB_1") (class "Default")
      (node (ref "JP4") (pin "7") (pinfunction "7_7") (pintype "passive"))
      (node (ref "R117") (pin "2") (pinfunction "2_2") (pintype "passive"))
    )
    (net (code "36") (name "LINBIASB_2") (class "Default")
      (node (ref "JP4") (pin "6") (pinfunction "6_6") (pintype "passive"))
      (node (ref "R73") (pin "1") (pinfunction "1_1") (pintype "passive"))
    )
    (net (code "37") (name "LINBIASB_3") (class "Default")
      (node (ref "JP4") (pin "5") (pinfunction "5_5") (pintype "passive"))
      (node (ref "R118") (pin "1") (pinfunction "1_1") (pintype "passive"))
    )
    (net (code "38") (name "LIN_NEG_A") (class "Default")
      (node (ref "D3") (pin "2") (pinfunction "C2_2") (pintype "passive"))
      (node (ref "R32") (pin "1") (pinfunction "1_1") (pintype "passive"))
    )
    (net (code "39") (name "LIN_NEG_B") (class "Default")
      (node (ref "D4") (pin "2") (pinfunction "C2_2") (pintype "passive"))
      (node (ref "R16") (pin "1") (pinfunction "1_1") (pintype "passive"))
    )
    (net (code "40") (name "LIN_POS_A") (class "Default")
      (node (ref "D3") (pin "1") (pinfunction "A1_1") (pintype "passive"))
      (node (ref "R55") (pin "1") (pinfunction "1_1") (pintype "passive"))
    )
    (net (code "41") (name "LIN_POS_B") (class "Default")
      (node (ref "D4") (pin "1") (pinfunction "A1_1") (pintype "passive"))
      (node (ref "R87") (pin "1") (pinfunction "1_1") (pintype "passive"))
    )
    (net (code "42") (name "Net-(C2-Pad1)") (class "Default")
      (node (ref "C2") (pin "1") (pinfunction "1_1") (pintype "passive"))
      (node (ref "R35") (pin "1") (pinfunction "1_1") (pintype "passive"))
    )
    (net (code "43") (name "Net-(C3-Pad1)") (class "Default")
      (node (ref "C3") (pin "1") (pinfunction "1_1") (pintype "passive"))
      (node (ref "R6") (pin "1") (pinfunction "1_1") (pintype "passive"))
    )
    (net (code "44") (name "Net-(C5-Pad1)") (class "Default")
      (node (ref "C5") (pin "1") (pinfunction "1_1") (pintype "passive"))
      (node (ref "R11") (pin "1") (pinfunction "1_1") (pintype "passive"))
    )
    (net (code "45") (name "Net-(C7-Pad1)") (class "Default")
      (node (ref "C7") (pin "1") (pinfunction "1_1") (pintype "passive"))
      (node (ref "R60") (pin "1") (pinfunction "1_1") (pintype "passive"))
    )
    (net (code "46") (name "Net-(C11-Pad1)") (class "Default")
      (node (ref "C11") (pin "1") (pinfunction "1_1") (pintype "passive"))
      (node (ref "R47") (pin "1") (pinfunction "1_1") (pintype "passive"))
    )
    (net (code "47") (name "Net-(C15-Pad1)") (class "Default")
      (node (ref "C15") (pin "1") (pinfunction "1_1") (pintype "passive"))
      (node (ref "R56") (pin "1") (pinfunction "1_1") (pintype "passive"))
    )
    (net (code "48") (name "Net-(C17-Pad1)") (class "Default")
      (node (ref "C17") (pin "1") (pinfunction "1_1") (pintype "passive"))
      (node (ref "R85") (pin "1") (pinfunction "1_1") (pintype "passive"))
    )
    (net (code "49") (name "Net-(C19-Pad1)") (class "Default")
      (node (ref "C19") (pin "1") (pinfunction "1_1") (pintype "passive"))
      (node (ref "R90") (pin "1") (pinfunction "1_1") (pintype "passive"))
    )
    (net (code "50") (name "Net-(CLAMP_REF-A)") (class "Default")
      (node (ref "CLAMP_REF") (pin "1") (pinfunction "A_1") (pintype "passive"))
      (node (ref "R63") (pin "2") (pinfunction "2_2") (pintype "passive"))
    )
    (net (code "51") (name "Net-(CLAMP_REF-E)") (class "Default")
      (node (ref "CLAMP_REF") (pin "3") (pinfunction "E_3") (pintype "passive"))
      (node (ref "R62") (pin "1") (pinfunction "1_1") (pintype "passive"))
    )
    (net (code "52") (name "Net-(CLAMP_REF-S)") (class "Default")
      (node (ref "C10") (pin "1") (pinfunction "1_1") (pintype "passive"))
      (node (ref "CLAMP_REF") (pin "2") (pinfunction "S_2") (pintype "passive"))
      (node (ref "IC4") (pin "3") (pinfunction "+IN_3") (pintype "input"))
    )
    (net (code "53") (name "Net-(D1-K1)") (class "Default")
      (node (ref "D1") (pin "1") (pinfunction "K1_1") (pintype "passive"))
      (node (ref "IC2") (pin "6") (pinfunction "CTRL_6") (pintype "input"))
      (node (ref "R44") (pin "1") (pinfunction "1_1") (pintype "passive"))
    )
    (net (code "54") (name "Net-(D1-K2)") (class "Default")
      (node (ref "D1") (pin "2") (pinfunction "K2_2") (pintype "passive"))
      (node (ref "IC2") (pin "11") (pinfunction "CTRL_11") (pintype "input"))
      (node (ref "R51") (pin "1") (pinfunction "1_1") (pintype "passive"))
    )
    (net (code "55") (name "Net-(D2-K1)") (class "Default")
      (node (ref "D2") (pin "1") (pinfunction "K1_1") (pintype "passive"))
      (node (ref "IC6") (pin "6") (pinfunction "CTRL_6") (pintype "input"))
      (node (ref "R70") (pin "1") (pinfunction "1_1") (pintype "passive"))
    )
    (net (code "56") (name "Net-(D2-K2)") (class "Default")
      (node (ref "D2") (pin "2") (pinfunction "K2_2") (pintype "passive"))
      (node (ref "IC6") (pin "11") (pinfunction "CTRL_11") (pintype "input"))
      (node (ref "R69") (pin "1") (pinfunction "1_1") (pintype "passive"))
    )
    (net (code "57") (name "Net-(D3-C1A2)") (class "Default")
      (node (ref "D3") (pin "3") (pinfunction "C1A2_3") (pintype "passive"))
      (node (ref "IC1") (pin "8") (pinfunction "OUT_8") (pintype "output"))
      (node (ref "R4") (pin "2") (pinfunction "2_2") (pintype "passive"))
    )
    (net (code "58") (name "Net-(D4-C1A2)") (class "Default")
      (node (ref "D4") (pin "3") (pinfunction "C1A2_3") (pintype "passive"))
      (node (ref "IC9") (pin "8") (pinfunction "OUT_8") (pintype "output"))
      (node (ref "R79") (pin "2") (pinfunction "2_2") (pintype "passive"))
    )
    (net (code "59") (name "Net-(D5-C1A2)") (class "Default")
      (node (ref "D5") (pin "3") (pinfunction "C1A2_3") (pintype "passive"))
      (node (ref "IC1") (pin "14") (pinfunction "OUT_14") (pintype "output"))
      (node (ref "R21") (pin "2") (pinfunction "2_2") (pintype "passive"))
    )
    (net (code "60") (name "Net-(D6-C1A2)") (class "Default")
      (node (ref "D6") (pin "3") (pinfunction "C1A2_3") (pintype "passive"))
      (node (ref "IC9") (pin "14") (pinfunction "OUT_14") (pintype "output"))
      (node (ref "R76") (pin "2") (pinfunction "2_2") (pintype "passive"))
    )
    (net (code "61") (name "Net-(IC1A--IN)") (class "Default")
      (node (ref "IC1") (pin "1") (pinfunction "OUT_1") (pintype "output"))
      (node (ref "IC1") (pin "2") (pinfunction "-IN_2") (pintype "input"))
      (node (ref "R12") (pin "1") (pinfunction "1_1") (pintype "passive"))
      (node (ref "R3") (pin "1") (pinfunction "1_1") (pintype "passive"))
    )
    (net (code "62") (name "Net-(IC1B--IN)") (class "Default")
      (node (ref "IC1") (pin "6") (pinfunction "-IN_6") (pintype "input"))
      (node (ref "IC1") (pin "7") (pinfunction "OUT_7") (pintype "output"))
      (node (ref "R22") (pin "1") (pinfunction "1_1") (pintype "passive"))
      (node (ref "R31") (pin "1") (pinfunction "1_1") (pintype "passive"))
    )
    (net (code "63") (name "Net-(IC1C--IN)") (class "Default")
      (node (ref "IC1") (pin "9") (pinfunction "-IN_9") (pintype "input"))
      (node (ref "R3") (pin "2") (pinfunction "2_2") (pintype "passive"))
      (node (ref "R4") (pin "1") (pinfunction "1_1") (pintype "passive"))
      (node (ref "R53") (pin "2") (pinfunction "2_2") (pintype "passive"))
      (node (ref "R8") (pin "1") (pinfunction "1_1") (pintype "passive"))
    )
    (net (code "64") (name "Net-(IC1D--IN)") (class "Default")
      (node (ref "IC1") (pin "13") (pinfunction "-IN_13") (pintype "input"))
      (node (ref "R14") (pin "1") (pinfunction "1_1") (pintype "passive"))
      (node (ref "R21") (pin "1") (pinfunction "1_1") (pintype "passive"))
      (node (ref "R31") (pin "2") (pinfunction "2_2") (pintype "passive"))
    )
    (net (code "65") (name "Net-(IC2A-IN)") (class "Default")
      (node (ref "IC2") (pin "2") (pinfunction "IN_2") (pintype "input"))
      (node (ref "R34") (pin "2") (pinfunction "2_2") (pintype "passive"))
      (node (ref "R35") (pin "2") (pinfunction "2_2") (pintype "passive"))
    )
    (net (code "66") (name "Net-(IC2A-OUT)") (class "Default")
      (node (ref "C13") (pin "2") (pinfunction "2_2") (pintype "passive"))
      (node (ref "IC2") (pin "4") (pinfunction "OUT_4") (pintype "output"))
      (node (ref "IC7") (pin "9") (pinfunction "-IN_9") (pintype "input"))
      (node (ref "R33") (pin "1") (pinfunction "1_1") (pintype "passive"))
    )
    (net (code "67") (name "Net-(IC2B-IN)") (class "Default")
      (node (ref "IC2") (pin "7") (pinfunction "IN_7") (pintype "input"))
      (node (ref "R5") (pin "2") (pinfunction "2_2") (pintype "passive"))
      (node (ref "R6") (pin "2") (pinfunction "2_2") (pintype "passive"))
    )
    (net (code "68") (name "Net-(IC2B-OUT)") (class "Default")
      (node (ref "C4") (pin "2") (pinfunction "2_2") (pintype "passive"))
      (node (ref "IC2") (pin "5") (pinfunction "OUT_5") (pintype "output"))
      (node (ref "IC5") (pin "6") (pinfunction "-IN_6") (pintype "input"))
      (node (ref "R10") (pin "1") (pinfunction "1_1") (pintype "passive"))
    )
    (net (code "69") (name "Net-(IC2C-IN)") (class "Default")
      (node (ref "IC2") (pin "10") (pinfunction "IN_10") (pintype "input"))
      (node (ref "R11") (pin "2") (pinfunction "2_2") (pintype "passive"))
      (node (ref "R7") (pin "2") (pinfunction "2_2") (pintype "passive"))
    )
    (net (code "70") (name "Net-(IC2C-OUT)") (class "Default")
      (node (ref "C12") (pin "2") (pinfunction "2_2") (pintype "passive"))
      (node (ref "IC2") (pin "12") (pinfunction "OUT_12") (pintype "output"))
      (node (ref "IC5") (pin "9") (pinfunction "-IN_9") (pintype "input"))
      (node (ref "R36") (pin "1") (pinfunction "1_1") (pintype "passive"))
    )
    (net (code "71") (name "Net-(IC2D-IN)") (class "Default")
      (node (ref "IC2") (pin "15") (pinfunction "IN_15") (pintype "input"))
      (node (ref "R59") (pin "2") (pinfunction "2_2") (pintype "passive"))
      (node (ref "R60") (pin "2") (pinfunction "2_2") (pintype "passive"))
    )
    (net (code "72") (name "Net-(IC2D-OUT)") (class "Default")
      (node (ref "C6") (pin "2") (pinfunction "2_2") (pintype "passive"))
      (node (ref "IC2") (pin "13") (pinfunction "OUT_13") (pintype "output"))
      (node (ref "IC7") (pin "13") (pinfunction "-IN_13") (pintype "input"))
      (node (ref "R58") (pin "1") (pinfunction "1_1") (pintype "passive"))
    )
    (net (code "73") (name "Net-(IC2E-MODE)") (class "Default")
      (node (ref "IC2") (pin "1") (pinfunction "MODE_1") (pintype "input"))
      (node (ref "R94") (pin "1") (pinfunction "1_1") (pintype "passive"))
    )
    (net (code "74") (name "Net-(IC3A--IN)") (class "Default")
      (node (ref "IC3") (pin "2") (pinfunction "-IN_2") (pintype "input"))
      (node (ref "R9") (pin "2") (pinfunction "2_2") (pintype "passive"))
    )
    (net (code "75") (name "Net-(IC3A-OUT)") (class "Default")
      (node (ref "IC3") (pin "1") (pinfunction "OUT_1") (pintype "output"))
      (node (ref "R24") (pin "2") (pinfunction "2_2") (pintype "passive"))
    )
    (net (code "76") (name "Net-(IC3B--IN)") (class "Default")
      (node (ref "IC3") (pin "6") (pinfunction "-IN_6") (pintype "input"))
      (node (ref "R48") (pin "1") (pinfunction "1_1") (pintype "passive"))
    )
    (net (code "77") (name "Net-(IC3B-OUT)") (class "Default")
      (node (ref "IC3") (pin "7") (pinfunction "OUT_7") (pintype "output"))
      (node (ref "R57") (pin "2") (pinfunction "2_2") (pintype "passive"))
    )
    (net (code "78") (name "Net-(IC3C--IN)") (class "Default")
      (node (ref "IC3") (pin "9") (pinfunction "-IN_9") (pintype "input"))
      (node (ref "R104") (pin "2") (pinfunction "2_2") (pintype "passive"))
    )
    (net (code "79") (name "Net-(IC3C-OUT)") (class "Default")
      (node (ref "IC3") (pin "8") (pinfunction "OUT_8") (pintype "output"))
      (node (ref "R105") (pin "1") (pinfunction "1_1") (pintype "passive"))
    )
    (net (code "80") (name "Net-(IC3D--IN)") (class "Default")
      (node (ref "IC3") (pin "13") (pinfunction "-IN_13") (pintype "input"))
      (node (ref "R109") (pin "1") (pinfunction "1_1") (pintype "passive"))
    )
    (net (code "81") (name "Net-(IC3D-OUT)") (class "Default")
      (node (ref "IC3") (pin "14") (pinfunction "OUT_14") (pintype "output"))
      (node (ref "R111") (pin "1") (pinfunction "1_1") (pintype "passive"))
    )
    (net (code "82") (name "Net-(IC4B-+IN)") (class "Default")
      (node (ref "C1") (pin "1") (pinfunction "1_1") (pintype "passive"))
      (node (ref "IC4") (pin "5") (pinfunction "+IN_5") (pintype "input"))
      (node (ref "OFFSET_LINA") (pin "2") (pinfunction "S_2") (pintype "passive"))
    )
    (net (code "83") (name "Net-(IC5B-OUT)") (class "Default")
      (node (ref "C4") (pin "1") (pinfunction "1_1") (pintype "passive"))
      (node (ref "IC5") (pin "7") (pinfunction "OUT_7") (pintype "output"))
      (node (ref "R10") (pin "2") (pinfunction "2_2") (pintype "passive"))
      (node (ref "R20") (pin "1") (pinfunction "1_1") (pintype "passive"))
      (node (ref "R48") (pin "2") (pinfunction "2_2") (pintype "passive"))
    )
    (net (code "84") (name "Net-(IC5C-OUT)") (class "Default")
      (node (ref "C12") (pin "1") (pinfunction "1_1") (pintype "passive"))
      (node (ref "IC5") (pin "8") (pinfunction "OUT_8") (pintype "output"))
      (node (ref "R29") (pin "1") (pinfunction "1_1") (pintype "passive"))
      (node (ref "R36") (pin "2") (pinfunction "2_2") (pintype "passive"))
      (node (ref "R9") (pin "1") (pinfunction "1_1") (pintype "passive"))
    )
    (net (code "85") (name "Net-(IC5D--IN)") (class "Default")
      (node (ref "IC5") (pin "13") (pinfunction "-IN_13") (pintype "input"))
      (node (ref "R28") (pin "1") (pinfunction "1_1") (pintype "passive"))
      (node (ref "R29") (pin "2") (pinfunction "2_2") (pintype "passive"))
    )
    (net (code "86") (name "Net-(IC5D-OUT)") (class "Default")
      (node (ref "IC5") (pin "14") (pinfunction "OUT_14") (pintype "output"))
      (node (ref "R126") (pin "1") (pinfunction "1_1") (pintype "passive"))
      (node (ref "R28") (pin "2") (pinfunction "2_2") (pintype "passive"))
    )
    (net (code "87") (name "Net-(IC6A-IN)") (class "Default")
      (node (ref "IC6") (pin "2") (pinfunction "IN_2") (pintype "input"))
      (node (ref "R89") (pin "2") (pinfunction "2_2") (pintype "passive"))
      (node (ref "R90") (pin "2") (pinfunction "2_2") (pintype "passive"))
    )
    (net (code "88") (name "Net-(IC6B-IN)") (class "Default")
      (node (ref "IC6") (pin "7") (pinfunction "IN_7") (pintype "input"))
      (node (ref "R54") (pin "2") (pinfunction "2_2") (pintype "passive"))
      (node (ref "R56") (pin "2") (pinfunction "2_2") (pintype "passive"))
    )
    (net (code "89") (name "Net-(IC6B-OUT)") (class "Default")
      (node (ref "C16") (pin "2") (pinfunction "2_2") (pintype "passive"))
      (node (ref "IC6") (pin "5") (pinfunction "OUT_5") (pintype "output"))
      (node (ref "IC8") (pin "6") (pinfunction "-IN_6") (pintype "input"))
      (node (ref "R64") (pin "1") (pinfunction "1_1") (pintype "passive"))
    )
    (net (code "90") (name "Net-(IC6C-IN)") (class "Default")
      (node (ref "IC6") (pin "10") (pinfunction "IN_10") (pintype "input"))
      (node (ref "R45") (pin "2") (pinfunction "2_2") (pintype "passive"))
      (node (ref "R47") (pin "2") (pinfunction "2_2") (pintype "passive"))
    )
    (net (code "91") (name "Net-(IC6C-OUT)") (class "Default")
      (node (ref "C14") (pin "2") (pinfunction "2_2") (pintype "passive"))
      (node (ref "IC6") (pin "12") (pinfunction "OUT_12") (pintype "output"))
      (node (ref "IC8") (pin "9") (pinfunction "-IN_9") (pintype "input"))
      (node (ref "R49") (pin "1") (pinfunction "1_1") (pintype "passive"))
    )
    (net (code "92") (name "Net-(IC6D-IN)") (class "Default")
      (node (ref "IC6") (pin "15") (pinfunction "IN_15") (pintype "input"))
      (node (ref "R84") (pin "2") (pinfunction "2_2") (pintype "passive"))
      (node (ref "R85") (pin "2") (pinfunction "2_2") (pintype "passive"))
    )
    (net (code "93") (name "Net-(IC6E-MODE)") (class "Default")
      (node (ref "IC6") (pin "1") (pinfunction "MODE_1") (pintype "input"))
      (node (ref "R110") (pin "1") (pinfunction "1_1") (pintype "passive"))
    )
    (net (code "94") (name "Net-(IC7A-+IN)") (class "Default")
      (node (ref "IC7") (pin "3") (pinfunction "+IN_3") (pintype "input"))
      (node (ref "R32") (pin "2") (pinfunction "2_2") (pintype "passive"))
    )
    (net (code "95") (name "Net-(IC7A--IN)") (class "Default")
      (node (ref "IC7") (pin "1") (pinfunction "OUT_1") (pintype "output"))
      (node (ref "IC7") (pin "2") (pinfunction "-IN_2") (pintype "input"))
      (node (ref "R33") (pin "2") (pinfunction "2_2") (pintype "passive"))
    )
    (net (code "96") (name "Net-(IC7B--IN)") (class "Default")
      (node (ref "IC7") (pin "6") (pinfunction "-IN_6") (pintype "input"))
      (node (ref "R18") (pin "1") (pinfunction "1_1") (pintype "passive"))
      (node (ref "R55") (pin "2") (pinfunction "2_2") (pintype "passive"))
    )
    (net (code "97") (name "Net-(IC7B-OUT)") (class "Default")
      (node (ref "IC7") (pin "7") (pinfunction "OUT_7") (pintype "output"))
      (node (ref "R18") (pin "2") (pinfunction "2_2") (pintype "passive"))
      (node (ref "R58") (pin "2") (pinfunction "2_2") (pintype "passive"))
    )
    (net (code "98") (name "Net-(IC8B-OUT)") (class "Default")
      (node (ref "C16") (pin "1") (pinfunction "1_1") (pintype "passive"))
      (node (ref "IC8") (pin "7") (pinfunction "OUT_7") (pintype "output"))
      (node (ref "R109") (pin "2") (pinfunction "2_2") (pintype "passive"))
      (node (ref "R64") (pin "2") (pinfunction "2_2") (pintype "passive"))
      (node (ref "R66") (pin "1") (pinfunction "1_1") (pintype "passive"))
    )
    (net (code "99") (name "Net-(IC8C-OUT)") (class "Default")
      (node (ref "C14") (pin "1") (pinfunction "1_1") (pintype "passive"))
      (node (ref "IC8") (pin "8") (pinfunction "OUT_8") (pintype "output"))
      (node (ref "R104") (pin "1") (pinfunction "1_1") (pintype "passive"))
      (node (ref "R49") (pin "2") (pinfunction "2_2") (pintype "passive"))
      (node (ref "R68") (pin "1") (pinfunction "1_1") (pintype "passive"))
    )
    (net (code "100") (name "Net-(IC8D--IN)") (class "Default")
      (node (ref "IC8") (pin "13") (pinfunction "-IN_13") (pintype "input"))
      (node (ref "R67") (pin "1") (pinfunction "1_1") (pintype "passive"))
      (node (ref "R68") (pin "2") (pinfunction "2_2") (pintype "passive"))
    )
    (net (code "101") (name "Net-(IC8D-OUT)") (class "Default")
      (node (ref "IC8") (pin "14") (pinfunction "OUT_14") (pintype "output"))
      (node (ref "R115") (pin "1") (pinfunction "1_1") (pintype "passive"))
      (node (ref "R67") (pin "2") (pinfunction "2_2") (pintype "passive"))
    )
    (net (code "102") (name "Net-(IC9A--IN)") (class "Default")
      (node (ref "IC9") (pin "1") (pinfunction "OUT_1") (pintype "output"))
      (node (ref "IC9") (pin "2") (pinfunction "-IN_2") (pintype "input"))
      (node (ref "R78") (pin "1") (pinfunction "1_1") (pintype "passive"))
      (node (ref "R80") (pin "1") (pinfunction "1_1") (pintype "passive"))
    )
    (net (code "103") (name "Net-(IC9B--IN)") (class "Default")
      (node (ref "IC9") (pin "6") (pinfunction "-IN_6") (pintype "input"))
      (node (ref "IC9") (pin "7") (pinfunction "OUT_7") (pintype "output"))
      (node (ref "R75") (pin "1") (pinfunction "1_1") (pintype "passive"))
      (node (ref "R77") (pin "1") (pinfunction "1_1") (pintype "passive"))
    )
    (net (code "104") (name "Net-(IC9C--IN)") (class "Default")
      (node (ref "IC9") (pin "9") (pinfunction "-IN_9") (pintype "input"))
      (node (ref "R73") (pin "2") (pinfunction "2_2") (pintype "passive"))
      (node (ref "R78") (pin "2") (pinfunction "2_2") (pintype "passive"))
      (node (ref "R79") (pin "1") (pinfunction "1_1") (pintype "passive"))
      (node (ref "R81") (pin "1") (pinfunction "1_1") (pintype "passive"))
    )
    (net (code "105") (name "Net-(IC9D--IN)") (class "Default")
      (node (ref "IC9") (pin "13") (pinfunction "-IN_13") (pintype "input"))
      (node (ref "R75") (pin "2") (pinfunction "2_2") (pintype "passive"))
      (node (ref "R76") (pin "1") (pinfunction "1_1") (pintype "passive"))
      (node (ref "R82") (pin "1") (pinfunction "1_1") (pintype "passive"))
    )
    (net (code "106") (name "Net-(IC10A-+IN)") (class "Default")
      (node (ref "IC10") (pin "3") (pinfunction "+IN_3") (pintype "input"))
      (node (ref "R16") (pin "2") (pinfunction "2_2") (pintype "passive"))
    )
    (net (code "107") (name "Net-(IC10A--IN)") (class "Default")
      (node (ref "IC10") (pin "1") (pinfunction "OUT_1") (pintype "output"))
      (node (ref "IC10") (pin "2") (pinfunction "-IN_2") (pintype "input"))
      (node (ref "R83") (pin "2") (pinfunction "2_2") (pintype "passive"))
    )
    (net (code "108") (name "Net-(IC10B--IN)") (class "Default")
      (node (ref "IC10") (pin "6") (pinfunction "-IN_6") (pintype "input"))
      (node (ref "R87") (pin "2") (pinfunction "2_2") (pintype "passive"))
      (node (ref "R92") (pin "1") (pinfunction "1_1") (pintype "passive"))
    )
    (net (code "109") (name "Net-(IC10B-OUT)") (class "Default")
      (node (ref "IC10") (pin "7") (pinfunction "OUT_7") (pintype "output"))
      (node (ref "R88") (pin "2") (pinfunction "2_2") (pintype "passive"))
      (node (ref "R92") (pin "2") (pinfunction "2_2") (pintype "passive"))
    )
    (net (code "110") (name "Net-(IC10C--IN)") (class "Default")
      (node (ref "C8") (pin "2") (pinfunction "2_2") (pintype "passive"))
      (node (ref "IC10") (pin "9") (pinfunction "-IN_9") (pintype "input"))
      (node (ref "IC6") (pin "13") (pinfunction "OUT_13") (pintype "output"))
      (node (ref "R83") (pin "1") (pinfunction "1_1") (pintype "passive"))
    )
    (net (code "111") (name "Net-(IC10D--IN)") (class "Default")
      (node (ref "C18") (pin "2") (pinfunction "2_2") (pintype "passive"))
      (node (ref "IC10") (pin "13") (pinfunction "-IN_13") (pintype "input"))
      (node (ref "IC6") (pin "4") (pinfunction "OUT_4") (pintype "output"))
      (node (ref "R88") (pin "1") (pinfunction "1_1") (pintype "passive"))
    )
    (net (code "112") (name "Net-(IC12A--IN)") (class "Default")
      (node (ref "IC12") (pin "2") (pinfunction "-IN_2") (pintype "input"))
      (node (ref "R100") (pin "2") (pinfunction "2_2") (pintype "passive"))
      (node (ref "R101") (pin "1") (pinfunction "1_1") (pintype "passive"))
    )
    (net (code "113") (name "Net-(IC12A-OUT)") (class "Default")
      (node (ref "IC12") (pin "1") (pinfunction "OUT_1") (pintype "output"))
      (node (ref "R100") (pin "1") (pinfunction "1_1") (pintype "passive"))
      (node (ref "R102") (pin "2") (pinfunction "2_2") (pintype "passive"))
    )
    (net (code "114") (name "Net-(IC12B-+IN)") (class "Default")
      (node (ref "IC12") (pin "5") (pinfunction "+IN_5") (pintype "input"))
      (node (ref "R95") (pin "1") (pinfunction "1_1") (pintype "passive"))
      (node (ref "R96") (pin "1") (pinfunction "1_1") (pintype "passive"))
    )
    (net (code "115") (name "Net-(IC12B--IN)") (class "Default")
      (node (ref "IC12") (pin "6") (pinfunction "-IN_6") (pintype "input"))
      (node (ref "R102") (pin "1") (pinfunction "1_1") (pintype "passive"))
      (node (ref "R46") (pin "1") (pinfunction "1_1") (pintype "passive"))
      (node (ref "R99") (pin "2") (pinfunction "2_2") (pintype "passive"))
    )
    (net (code "116") (name "Net-(IC12C-+IN)") (class "Default")
      (node (ref "IC12") (pin "10") (pinfunction "+IN_10") (pintype "input"))
      (node (ref "R103") (pin "1") (pinfunction "1_1") (pintype "passive"))
      (node (ref "R98") (pin "1") (pinfunction "1_1") (pintype "passive"))
    )
    (net (code "117") (name "Net-(IC12C--IN)") (class "Default")
      (node (ref "IC12") (pin "9") (pinfunction "-IN_9") (pintype "input"))
      (node (ref "R107") (pin "1") (pinfunction "1_1") (pintype "passive"))
      (node (ref "R108") (pin "2") (pinfunction "2_2") (pintype "passive"))
      (node (ref "R97") (pin "1") (pinfunction "1_1") (pintype "passive"))
    )
    (net (code "118") (name "Net-(IC12D--IN)") (class "Default")
      (node (ref "IC12") (pin "13") (pinfunction "-IN_13") (pintype "input"))
      (node (ref "R113") (pin "1") (pinfunction "1_1") (pintype "passive"))
      (node (ref "R114") (pin "2") (pinfunction "2_2") (pintype "passive"))
    )
    (net (code "119") (name "Net-(IC14A--IN)") (class "Default")
      (node (ref "IC14") (pin "2") (pinfunction "-IN_2") (pintype "input"))
      (node (ref "R39") (pin "2") (pinfunction "2_2") (pintype "passive"))
      (node (ref "R42") (pin "1") (pinfunction "1_1") (pintype "passive"))
    )
    (net (code "120") (name "Net-(IC14A-OUT)") (class "Default")
      (node (ref "IC14") (pin "1") (pinfunction "OUT_1") (pintype "output"))
      (node (ref "R15") (pin "2") (pinfunction "2_2") (pintype "passive"))
      (node (ref "R39") (pin "1") (pinfunction "1_1") (pintype "passive"))
    )
    (net (code "121") (name "Net-(IC14B-+IN)") (class "Default")
      (node (ref "IC14") (pin "5") (pinfunction "+IN_5") (pintype "input"))
      (node (ref "R26") (pin "1") (pinfunction "1_1") (pintype "passive"))
      (node (ref "R27") (pin "1") (pinfunction "1_1") (pintype "passive"))
    )
    (net (code "122") (name "Net-(IC14B--IN)") (class "Default")
      (node (ref "IC14") (pin "6") (pinfunction "-IN_6") (pintype "input"))
      (node (ref "R106") (pin "1") (pinfunction "1_1") (pintype "passive"))
      (node (ref "R15") (pin "1") (pinfunction "1_1") (pintype "passive"))
      (node (ref "R38") (pin "2") (pinfunction "2_2") (pintype "passive"))
    )
    (net (code "123") (name "Net-(IC14C-+IN)") (class "Default")
      (node (ref "IC14") (pin "10") (pinfunction "+IN_10") (pintype "input"))
      (node (ref "R41") (pin "1") (pinfunction "1_1") (pintype "passive"))
      (node (ref "R43") (pin "1") (pinfunction "1_1") (pintype "passive"))
    )
    (net (code "124") (name "Net-(IC14C--IN)") (class "Default")
      (node (ref "IC14") (pin "9") (pinfunction "-IN_9") (pintype "input"))
      (node (ref "R19") (pin "2") (pinfunction "2_2") (pintype "passive"))
      (node (ref "R23") (pin "1") (pinfunction "1_1") (pintype "passive"))
      (node (ref "R40") (pin "1") (pinfunction "1_1") (pintype "passive"))
    )
    (net (code "125") (name "Net-(IC14D--IN)") (class "Default")
      (node (ref "IC14") (pin "13") (pinfunction "-IN_13") (pintype "input"))
      (node (ref "R17") (pin "1") (pinfunction "1_1") (pintype "passive"))
      (node (ref "R25") (pin "2") (pinfunction "2_2") (pintype "passive"))
    )
    (net (code "126") (name "Net-(LED_REF-E)") (class "Default")
      (node (ref "LED_REF") (pin "3") (pinfunction "E_3") (pintype "passive"))
      (node (ref "R112") (pin "1") (pinfunction "1_1") (pintype "passive"))
    )
    (net (code "127") (name "Net-(LED_REF-S)") (class "Default")
      (node (ref "C20") (pin "1") (pinfunction "1_1") (pintype "passive"))
      (node (ref "LED_REF") (pin "2") (pinfunction "S_2") (pintype "passive"))
      (node (ref "R113") (pin "2") (pinfunction "2_2") (pintype "passive"))
    )
    (net (code "128") (name "Net-(OFFSET_LINA-E)") (class "Default")
      (node (ref "OFFSET_LINA") (pin "3") (pinfunction "E_3") (pintype "passive"))
      (node (ref "R13") (pin "1") (pinfunction "1_1") (pintype "passive"))
    )
    (net (code "129") (name "Net-(OFFSET_REF-E)") (class "Default")
      (node (ref "OFFSET_REF") (pin "3") (pinfunction "E_3") (pintype "passive"))
      (node (ref "R2") (pin "1") (pinfunction "1_1") (pintype "passive"))
    )
    (net (code "130") (name "Net-(OFFSET_REF-S)") (class "Default")
      (node (ref "C9") (pin "1") (pinfunction "1_1") (pintype "passive"))
      (node (ref "OFFSET_REF") (pin "2") (pinfunction "S_2") (pintype "passive"))
      (node (ref "R17") (pin "2") (pinfunction "2_2") (pintype "passive"))
    )
    (net (code "131") (name "Net-(Q9-D)") (class "Default")
      (node (ref "JP8") (pin "1") (pinfunction "1_1") (pintype "passive"))
      (node (ref "JP8") (pin "2") (pinfunction "2_2") (pintype "passive"))
      (node (ref "Q9") (pin "3") (pinfunction "D_3") (pintype "passive"))
    )
    (net (code "132") (name "Net-(Q10-D)") (class "Default")
      (node (ref "JP8") (pin "10") (pinfunction "10_10") (pintype "passive"))
      (node (ref "JP8") (pin "9") (pinfunction "9_9") (pintype "passive"))
      (node (ref "Q10") (pin "3") (pinfunction "D_3") (pintype "passive"))
    )
    (net (code "133") (name "Net-(R123-Pad2)") (class "Default")
      (node (ref "R123") (pin "2") (pinfunction "2_2") (pintype "passive"))
      (node (ref "R34") (pin "1") (pinfunction "1_1") (pintype "passive"))
      (node (ref "R37") (pin "1") (pinfunction "1_1") (pintype "passive"))
    )
    (net (code "134") (name "Net-(R124-Pad2)") (class "Default")
      (node (ref "R124") (pin "2") (pinfunction "2_2") (pintype "passive"))
      (node (ref "R84") (pin "1") (pinfunction "1_1") (pintype "passive"))
      (node (ref "R86") (pin "1") (pinfunction "1_1") (pintype "passive"))
    )
    (net (code "135") (name "Net-(R125-Pad2)") (class "Default")
      (node (ref "R125") (pin "2") (pinfunction "2_2") (pintype "passive"))
      (node (ref "R89") (pin "1") (pinfunction "1_1") (pintype "passive"))
      (node (ref "R91") (pin "1") (pinfunction "1_1") (pintype "passive"))
    )
    (net (code "136") (name "Net-(R127-Pad2)") (class "Default")
      (node (ref "R127") (pin "2") (pinfunction "2_2") (pintype "passive"))
      (node (ref "R59") (pin "1") (pinfunction "1_1") (pintype "passive"))
      (node (ref "R61") (pin "1") (pinfunction "1_1") (pintype "passive"))
    )
    (net (code "137") (name "OFFSET_LIN") (class "Default")
      (node (ref "IC10") (pin "10") (pinfunction "+IN_10") (pintype "input"))
      (node (ref "IC10") (pin "12") (pinfunction "+IN_12") (pintype "input"))
      (node (ref "IC4") (pin "6") (pinfunction "-IN_6") (pintype "input"))
      (node (ref "IC4") (pin "7") (pinfunction "OUT_7") (pintype "output"))
      (node (ref "IC7") (pin "10") (pinfunction "+IN_10") (pintype "input"))
      (node (ref "IC7") (pin "12") (pinfunction "+IN_12") (pintype "input"))
    )
    (net (code "138") (name "OFFSET_REF") (class "Default")
      (node (ref "IC14") (pin "14") (pinfunction "OUT_14") (pintype "output"))
      (node (ref "R106") (pin "2") (pinfunction "2_2") (pintype "passive"))
      (node (ref "R23") (pin "2") (pinfunction "2_2") (pintype "passive"))
      (node (ref "R25") (pin "1") (pinfunction "1_1") (pintype "passive"))
      (node (ref "R46") (pin "2") (pinfunction "2_2") (pintype "passive"))
      (node (ref "R97") (pin "2") (pinfunction "2_2") (pintype "passive"))
    )
    (net (code "139") (name "OUT_A") (class "Default")
      (node (ref "JP7") (pin "1") (pinfunction "1_1") (pintype "passive"))
      (node (ref "R126") (pin "2") (pinfunction "2_2") (pintype "passive"))
    )
    (net (code "140") (name "OUT_B") (class "Default")
      (node (ref "JP7") (pin "5") (pinfunction "5_5") (pintype "passive"))
      (node (ref "R115") (pin "2") (pinfunction "2_2") (pintype "passive"))
    )
    (net (code "141") (name "POT_EXPA_1") (class "Default")
      (node (ref "IC1") (pin "12") (pinfunction "+IN_12") (pintype "input"))
      (node (ref "JP2") (pin "4") (pinfunction "4_4") (pintype "passive"))
      (node (ref "R22") (pin "2") (pinfunction "2_2") (pintype "passive"))
    )
    (net (code "142") (name "POT_EXPA_3") (class "Default")
      (node (ref "JP2") (pin "3") (pinfunction "3_3") (pintype "passive"))
      (node (ref "R14") (pin "2") (pinfunction "2_2") (pintype "passive"))
    )
    (net (code "143") (name "POT_EXPB_1") (class "Default")
      (node (ref "IC9") (pin "12") (pinfunction "+IN_12") (pintype "input"))
      (node (ref "JP2") (pin "2") (pinfunction "2_2") (pintype "passive"))
      (node (ref "R77") (pin "2") (pinfunction "2_2") (pintype "passive"))
    )
    (net (code "144") (name "POT_EXPB_3") (class "Default")
      (node (ref "JP2") (pin "1") (pinfunction "1_1") (pintype "passive"))
      (node (ref "R82") (pin "2") (pinfunction "2_2") (pintype "passive"))
    )
    (net (code "145") (name "POT_LINA_1") (class "Default")
      (node (ref "IC1") (pin "10") (pinfunction "+IN_10") (pintype "input"))
      (node (ref "JP2") (pin "9") (pinfunction "9_9") (pintype "passive"))
      (node (ref "R12") (pin "2") (pinfunction "2_2") (pintype "passive"))
    )
    (net (code "146") (name "POT_LINA_3") (class "Default")
      (node (ref "JP2") (pin "8") (pinfunction "8_8") (pintype "passive"))
      (node (ref "R8") (pin "2") (pinfunction "2_2") (pintype "passive"))
    )
    (net (code "147") (name "POT_LINB_1") (class "Default")
      (node (ref "IC9") (pin "10") (pinfunction "+IN_10") (pintype "input"))
      (node (ref "JP2") (pin "7") (pinfunction "7_7") (pintype "passive"))
      (node (ref "R80") (pin "2") (pinfunction "2_2") (pintype "passive"))
    )
    (net (code "148") (name "POT_LINB_3") (class "Default")
      (node (ref "JP2") (pin "6") (pinfunction "6_6") (pintype "passive"))
      (node (ref "R81") (pin "2") (pinfunction "2_2") (pintype "passive"))
    )
    (net (code "149") (name "UNIPOLAR_A") (class "Default")
      (node (ref "JP6") (pin "1") (pinfunction "1_1") (pintype "passive"))
      (node (ref "R119") (pin "1") (pinfunction "1_1") (pintype "passive"))
    )
    (net (code "150") (name "UNIPOLAR_B") (class "Default")
      (node (ref "JP6") (pin "4") (pinfunction "4_4") (pintype "passive"))
      (node (ref "R120") (pin "1") (pinfunction "1_1") (pintype "passive"))
    )
    (net (code "151") (name "V_REF") (class "Default")
      (node (ref "IC13") (pin "1") (pinfunction "C_1") (pintype "passive"))
      (node (ref "R112") (pin "2") (pinfunction "2_2") (pintype "passive"))
      (node (ref "R13") (pin "2") (pinfunction "2_2") (pintype "passive"))
      (node (ref "R2") (pin "2") (pinfunction "2_2") (pintype "passive"))
      (node (ref "R37") (pin "2") (pinfunction "2_2") (pintype "passive"))
      (node (ref "R61") (pin "2") (pinfunction "2_2") (pintype "passive"))
      (node (ref "R62") (pin "2") (pinfunction "2_2") (pintype "passive"))
      (node (ref "R86") (pin "2") (pinfunction "2_2") (pintype "passive"))
      (node (ref "R91") (pin "2") (pinfunction "2_2") (pintype "passive"))
      (node (ref "R93") (pin "1") (pinfunction "1_1") (pintype "passive"))
    )
  )
)
